# permamote.net
KiCad netlist of a schematic drawn in EAGLE
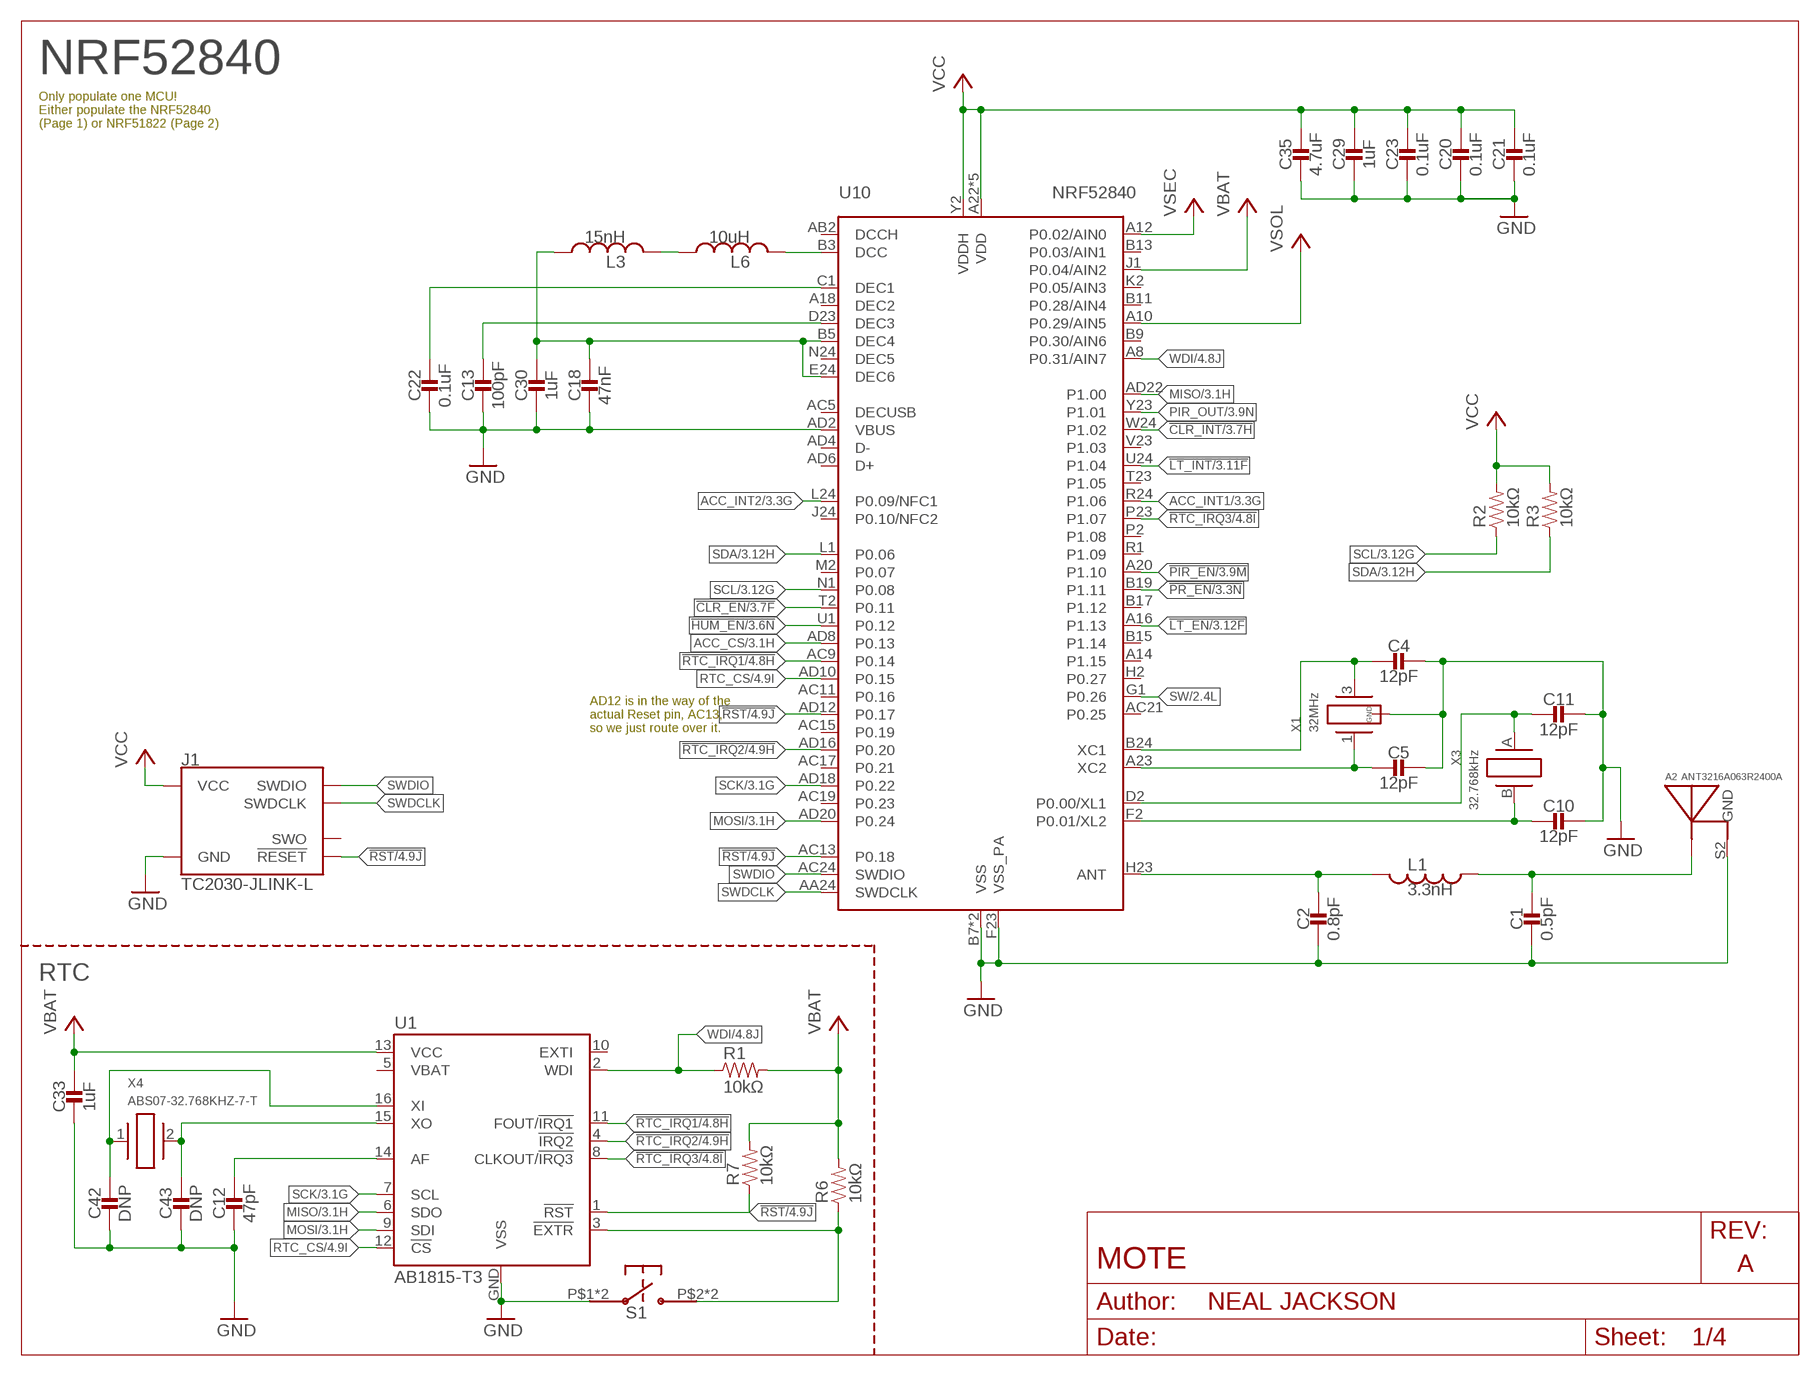
[diagram p0: schematic, sheet 1]
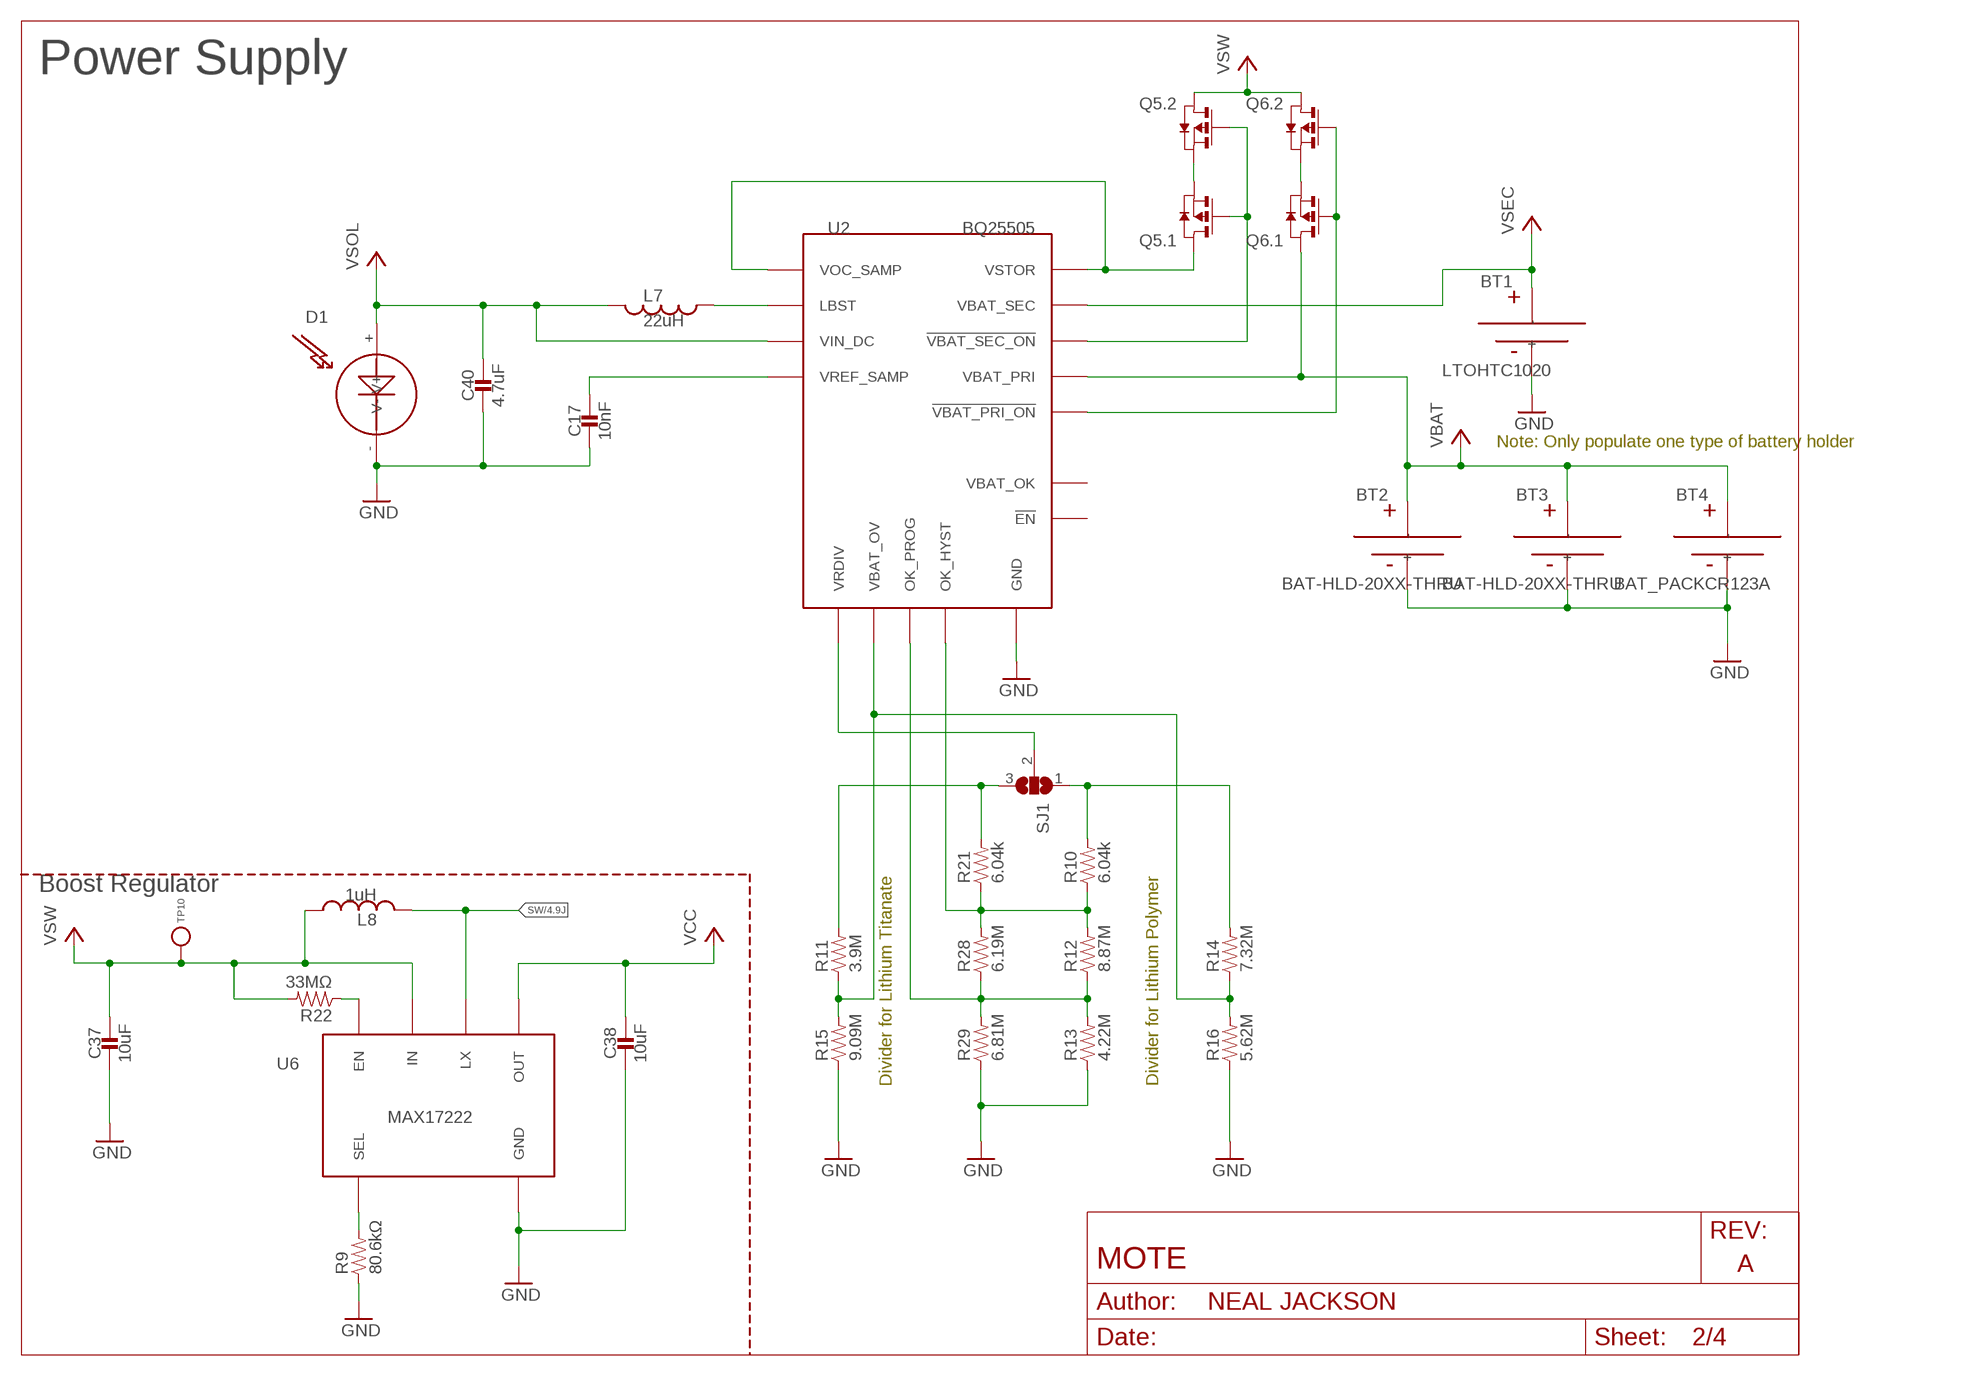
[diagram p1: schematic, sheet 2]
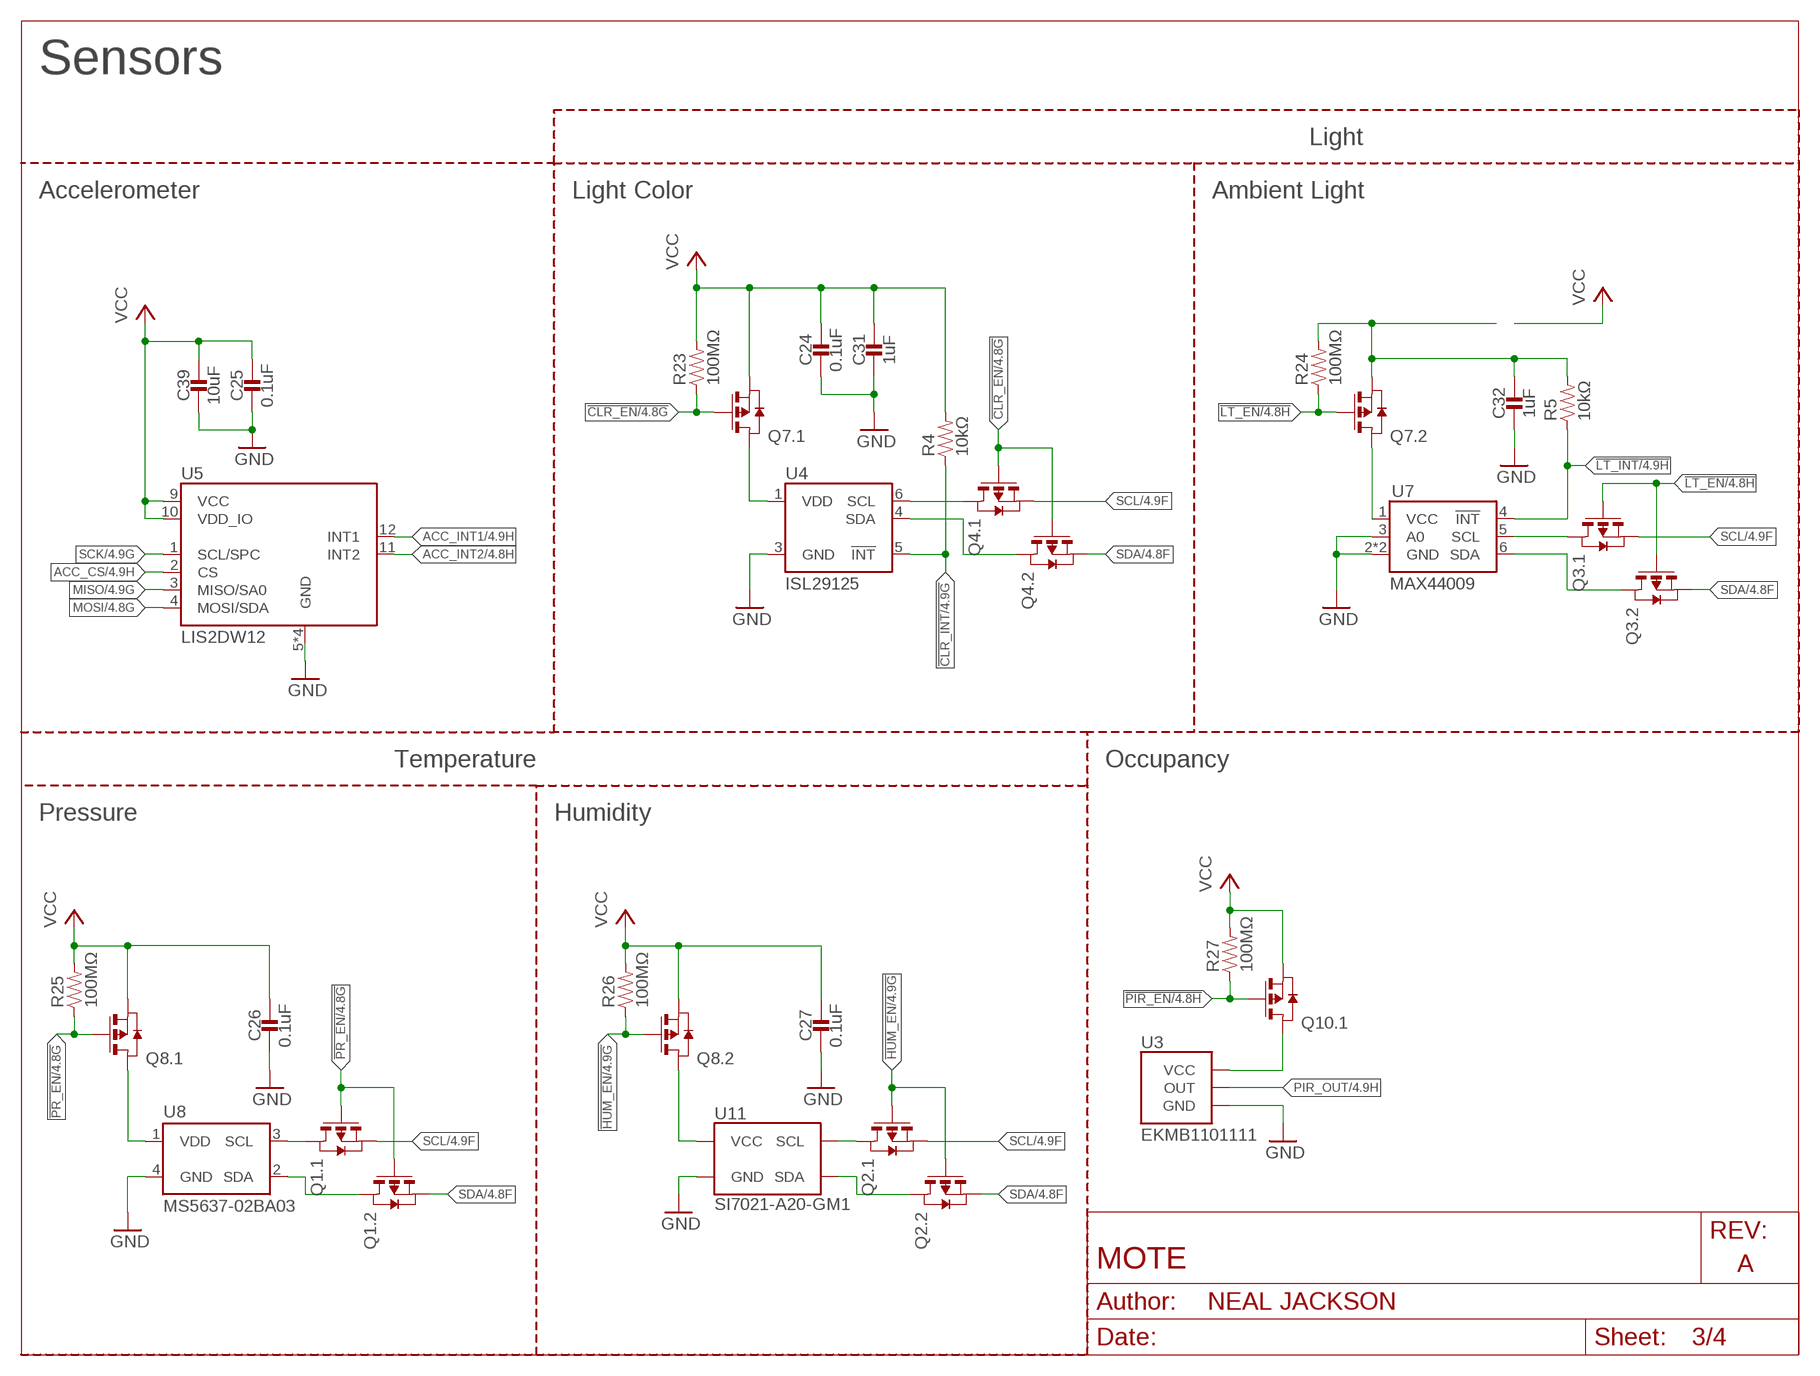
[diagram p2: schematic, sheet 3]
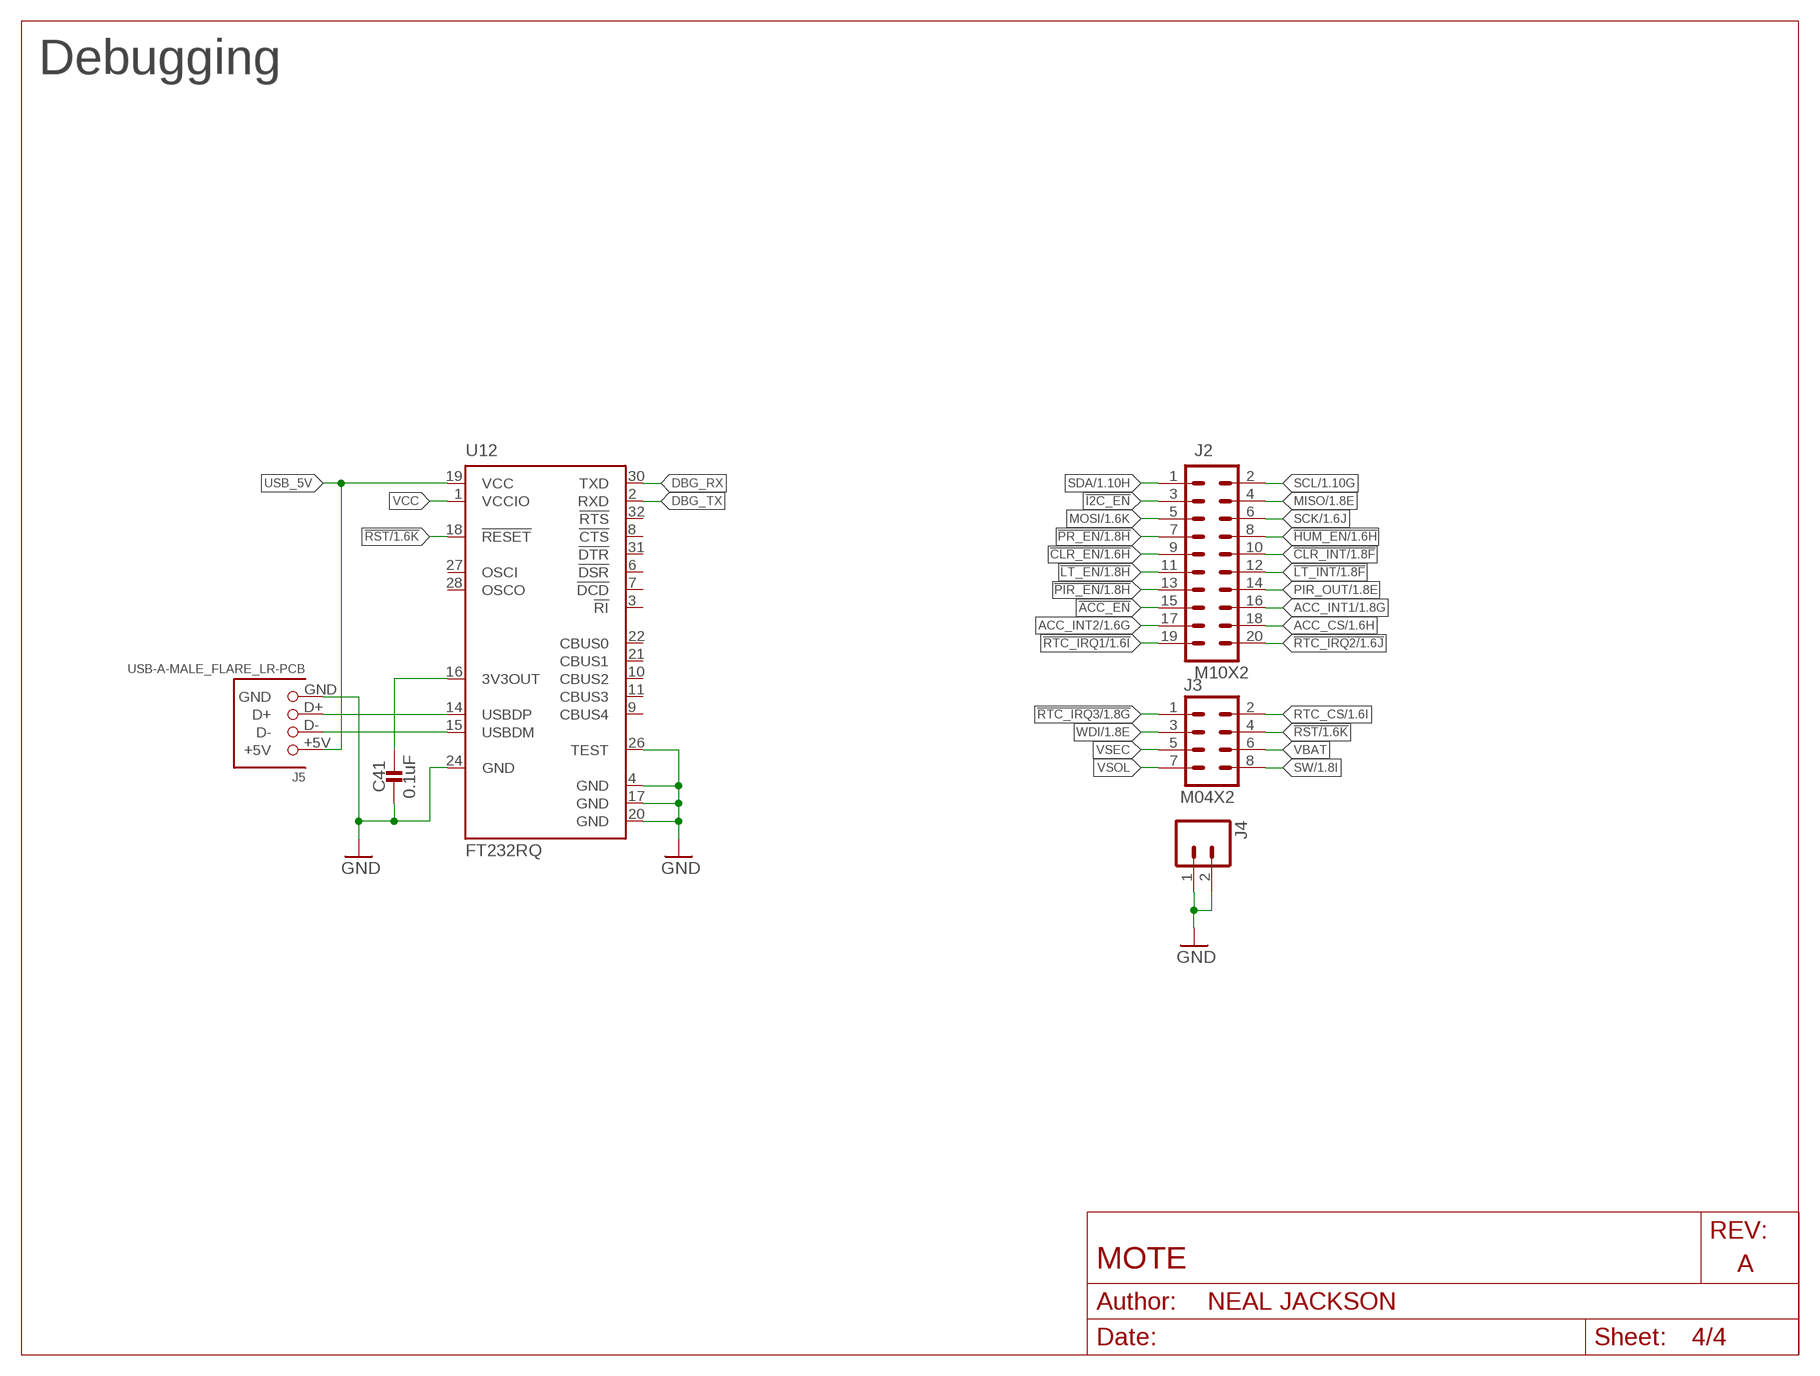
[diagram p3: schematic, sheet 4]

(export (version "E")
  (design (tool "Eeschema 10.0.6"))
  (components
    (comp (ref "BT1")
      (value "LTOHTC1020")
      (footprint "eagle-import:1020")
      (libsource (lib "eagle-import") (part "LTOHTC1020"))
    )
    (comp (ref "BT2")
      (value "BAT-HLD-20XX-THRU")
      (footprint "eagle-import:BAT-HLD-20XX-THRU")
      (fields (field (name "MANUFACTURER") "Linx Technologies") (field (name "MPN") "BAT-HLD-001-THM"))
      (libsource (lib "eagle-import") (part "BAT-HLD-20XX-THRU"))
    )
    (comp (ref "BT3")
      (value "BAT-HLD-20XX-THRU")
      (footprint "eagle-import:BAT-HLD-20XX-THRU")
      (fields (field (name "MANUFACTURER") "Linx Technologies") (field (name "MPN") "BAT-HLD-001-THM"))
      (libsource (lib "eagle-import") (part "BAT-HLD-20XX-THRU"))
    )
    (comp (ref "BT4")
      (value "BAT_PACKCR123A")
      (footprint "eagle-import:BH123A")
      (fields (field (name "MANUFACTURER") "MPD") (field (name "MPN") "BH123A"))
      (libsource (lib "eagle-import") (part "BAT_PACKCR123A"))
    )
    (comp (ref "C17")
      (value "10nF")
      (footprint "eagle-import:0603_CAP")
      (libsource (lib "eagle-import") (part "CAPACITOR0603_CAP"))
    )
    (comp (ref "C37")
      (value "10uF")
      (footprint "eagle-import:0603_CAP")
      (libsource (lib "eagle-import") (part "CAPACITOR0603_CAP"))
    )
    (comp (ref "C38")
      (value "10uF")
      (footprint "eagle-import:0603_CAP")
      (libsource (lib "eagle-import") (part "CAPACITOR0603_CAP"))
    )
    (comp (ref "C40")
      (value "4.7uF")
      (footprint "eagle-import:0603_CAP")
      (libsource (lib "eagle-import") (part "CAPACITOR0603_CAP"))
    )
    (comp (ref "D1")
      (value "SOLARCELL")
      (footprint "eagle-import:SOLAR_HOLES")
      (libsource (lib "eagle-import") (part "SOLARCELL"))
    )
    (comp (ref "L7")
      (value "22uH")
      (footprint "eagle-import:74437324220")
      (fields (field (name "DIGIKEY") "732-3340-1-ND"))
      (libsource (lib "eagle-import") (part "INDUCTOR74437324220"))
    )
    (comp (ref "L8")
      (value "1uH")
      (footprint "eagle-import:IHL-1212BZ-11")
      (fields
        (field (name "MANUFACTURER") "Vishay Dale")
        (field (name "MPN") "IHLP1212BZER2R2M11")
        (field (name "DIGIKEY") "541-1319-1-ND")
        (field (name "MPN_1") "IHLP1212BZER1R0M11")
      )
      (libsource (lib "eagle-import") (part "INDUCTORIHL"))
    )
    (comp (ref "Q5")
      (value "PMDXB950UPEL")
      (footprint "eagle-import:XDFN-6")
      (fields (field (name "MANUFACTURER") "NEXPERIA") (field (name "MPN") "PMDXB950UPELZ"))
      (libsource (lib "eagle-import") (part "PMDXB950UPEL"))
    )
    (comp (ref "Q6")
      (value "PMDXB950UPEL")
      (footprint "eagle-import:XDFN-6")
      (fields (field (name "MANUFACTURER") "NEXPERIA") (field (name "MPN") "PMDXB950UPELZ"))
      (libsource (lib "eagle-import") (part "PMDXB950UPEL"))
    )
    (comp (ref "R9")
      (value "80.6kΩ")
      (footprint "eagle-import:0603-RES")
      (libsource (lib "eagle-import") (part "RESISTOR0603_RES"))
    )
    (comp (ref "R10")
      (value "6.04k")
      (footprint "eagle-import:0402_RES")
      (libsource (lib "eagle-import") (part "RESISTOR0402_RES"))
    )
    (comp (ref "R11")
      (value "3.9M")
      (footprint "eagle-import:0402_RES")
      (libsource (lib "eagle-import") (part "RESISTOR0402_RES"))
    )
    (comp (ref "R12")
      (value "8.87M")
      (footprint "eagle-import:0402_RES")
      (libsource (lib "eagle-import") (part "RESISTOR0402_RES"))
    )
    (comp (ref "R13")
      (value "4.22M")
      (footprint "eagle-import:0402_RES")
      (libsource (lib "eagle-import") (part "RESISTOR0402_RES"))
    )
    (comp (ref "R14")
      (value "7.32M")
      (footprint "eagle-import:0402_RES")
      (libsource (lib "eagle-import") (part "RESISTOR0402_RES"))
    )
    (comp (ref "R15")
      (value "9.09M")
      (footprint "eagle-import:0402_RES")
      (libsource (lib "eagle-import") (part "RESISTOR0402_RES"))
    )
    (comp (ref "R16")
      (value "5.62M")
      (footprint "eagle-import:0402_RES")
      (libsource (lib "eagle-import") (part "RESISTOR0402_RES"))
    )
    (comp (ref "R21")
      (value "6.04k")
      (footprint "eagle-import:0402_RES")
      (libsource (lib "eagle-import") (part "RESISTOR0402_RES"))
    )
    (comp (ref "R22")
      (value "33MΩ")
      (footprint "eagle-import:0603-RES")
      (libsource (lib "eagle-import") (part "RESISTOR0603_RES"))
    )
    (comp (ref "R28")
      (value "6.19M")
      (footprint "eagle-import:0402_RES")
      (libsource (lib "eagle-import") (part "RESISTOR0402_RES"))
    )
    (comp (ref "R29")
      (value "6.81M")
      (footprint "eagle-import:0402_RES")
      (libsource (lib "eagle-import") (part "RESISTOR0402_RES"))
    )
    (comp (ref "SJ1")
      (value "SJ2W")
      (footprint "eagle-import:SJ_2")
      (libsource (lib "eagle-import") (part "SJ2W"))
    )
    (comp (ref "TP10")
      (value "TEST_POINT_0.040IN")
      (footprint "eagle-import:TESTPOINT_0.040IN")
      (libsource (lib "eagle-import") (part "TEST_POINT_0.040IN"))
    )
    (comp (ref "U2")
      (value "BQ25505")
      (footprint "eagle-import:S-PVQFN-N20-RGR")
      (fields (field (name "MANUFACTURER") "TI") (field (name "MPN") "BQ25505RGRR"))
      (libsource (lib "eagle-import") (part "BQ25505"))
    )
    (comp (ref "U6")
      (value "MAX17222")
      (footprint "eagle-import:UDFN-6-MAXIM")
      (fields (field (name "MANUFACTURER") "MAXIM INTEGRATED") (field (name "MPN") "MAX17222ELT+T"))
      (libsource (lib "eagle-import") (part "MAX17222"))
    )
    (comp (ref "C24")
      (value "0.1uF")
      (footprint "eagle-import:0402_CAP")
      (libsource (lib "eagle-import") (part "CAPACITOR0402_CAP"))
    )
    (comp (ref "C25")
      (value "0.1uF")
      (footprint "eagle-import:0402_CAP")
      (libsource (lib "eagle-import") (part "CAPACITOR0402_CAP"))
    )
    (comp (ref "C26")
      (value "0.1uF")
      (footprint "eagle-import:0402_CAP")
      (libsource (lib "eagle-import") (part "CAPACITOR0402_CAP"))
    )
    (comp (ref "C27")
      (value "0.1uF")
      (footprint "eagle-import:0402_CAP")
      (libsource (lib "eagle-import") (part "CAPACITOR0402_CAP"))
    )
    (comp (ref "C31")
      (value "1uF")
      (footprint "eagle-import:0402_CAP")
      (libsource (lib "eagle-import") (part "CAPACITOR0402_CAP"))
    )
    (comp (ref "C32")
      (value "1uF")
      (footprint "eagle-import:0402_CAP")
      (libsource (lib "eagle-import") (part "CAPACITOR0402_CAP"))
    )
    (comp (ref "C39")
      (value "10uF")
      (footprint "eagle-import:0603_CAP")
      (libsource (lib "eagle-import") (part "CAPACITOR0603_CAP"))
    )
    (comp (ref "Q1")
      (value "PMDXB950UPEL")
      (footprint "eagle-import:XDFN-6")
      (fields (field (name "MANUFACTURER") "NEXPERIA") (field (name "MPN") "PMDXB950UPELZ"))
      (libsource (lib "eagle-import") (part "PMDXB950UPEL"))
    )
    (comp (ref "Q2")
      (value "PMDXB950UPEL")
      (footprint "eagle-import:XDFN-6")
      (fields (field (name "MANUFACTURER") "NEXPERIA") (field (name "MPN") "PMDXB950UPELZ"))
      (libsource (lib "eagle-import") (part "PMDXB950UPEL"))
    )
    (comp (ref "Q3")
      (value "PMDXB950UPEL")
      (footprint "eagle-import:XDFN-6")
      (fields (field (name "MANUFACTURER") "NEXPERIA") (field (name "MPN") "PMDXB950UPELZ"))
      (libsource (lib "eagle-import") (part "PMDXB950UPEL"))
    )
    (comp (ref "Q4")
      (value "PMDXB950UPEL")
      (footprint "eagle-import:XDFN-6")
      (fields (field (name "MANUFACTURER") "NEXPERIA") (field (name "MPN") "PMDXB950UPELZ"))
      (libsource (lib "eagle-import") (part "PMDXB950UPEL"))
    )
    (comp (ref "Q7")
      (value "PMDXB950UPEL")
      (footprint "eagle-import:XDFN-6")
      (fields (field (name "MANUFACTURER") "NEXPERIA") (field (name "MPN") "PMDXB950UPELZ"))
      (libsource (lib "eagle-import") (part "PMDXB950UPEL"))
    )
    (comp (ref "Q8")
      (value "PMDXB950UPEL")
      (footprint "eagle-import:XDFN-6")
      (fields (field (name "MANUFACTURER") "NEXPERIA") (field (name "MPN") "PMDXB950UPELZ"))
      (libsource (lib "eagle-import") (part "PMDXB950UPEL"))
    )
    (comp (ref "Q10")
      (value "PMDXB950UPEL")
      (footprint "eagle-import:XDFN-6")
      (fields (field (name "MANUFACTURER") "NEXPERIA") (field (name "MPN") "PMDXB950UPELZ"))
      (libsource (lib "eagle-import") (part "PMDXB950UPEL"))
    )
    (comp (ref "R4")
      (value "10kΩ")
      (footprint "eagle-import:0402_RES")
      (libsource (lib "eagle-import") (part "RESISTOR0402_RES"))
    )
    (comp (ref "R5")
      (value "10kΩ")
      (footprint "eagle-import:0402_RES")
      (libsource (lib "eagle-import") (part "RESISTOR0402_RES"))
    )
    (comp (ref "R23")
      (value "100MΩ")
      (footprint "eagle-import:0402_RES")
      (libsource (lib "eagle-import") (part "RESISTOR0402_RES"))
    )
    (comp (ref "R24")
      (value "100MΩ")
      (footprint "eagle-import:0402_RES")
      (libsource (lib "eagle-import") (part "RESISTOR0402_RES"))
    )
    (comp (ref "R25")
      (value "100MΩ")
      (footprint "eagle-import:0402_RES")
      (libsource (lib "eagle-import") (part "RESISTOR0402_RES"))
    )
    (comp (ref "R26")
      (value "100MΩ")
      (footprint "eagle-import:0402_RES")
      (libsource (lib "eagle-import") (part "RESISTOR0402_RES"))
    )
    (comp (ref "R27")
      (value "100MΩ")
      (footprint "eagle-import:0402_RES")
      (libsource (lib "eagle-import") (part "RESISTOR0402_RES"))
    )
    (comp (ref "U3")
      (value "EKMB1101111")
      (footprint "eagle-import:AMN2")
      (fields (field (name "MANUFACTURER") "PANASONIC"))
      (libsource (lib "eagle-import") (part "EKMB1101111"))
    )
    (comp (ref "U4")
      (value "ISL29125")
      (footprint "eagle-import:ODFN-6-1.5MMX1.6MM")
      (fields (field (name "MANUFACTURER") "INTERSIL") (field (name "MPN") "ISL29125IROZ-T7A"))
      (libsource (lib "eagle-import") (part "ISL29125"))
    )
    (comp (ref "U5")
      (value "LIS2DW12")
      (footprint "eagle-import:LGA-12")
      (fields (field (name "MANUFACTURER") "STMicroelectronics") (field (name "MPN") "LIS2DW12TR"))
      (libsource (lib "eagle-import") (part "LIS2DW12"))
    )
    (comp (ref "U7")
      (value "MAX44009")
      (footprint "eagle-import:UDFN-6-EXPOSED")
      (fields (field (name "MANUFACTURER") "MAXIM") (field (name "MPN") "MAX44009EDT+T"))
      (libsource (lib "eagle-import") (part "MAX44009"))
    )
    (comp (ref "U8")
      (value "MS5637-02BA03")
      (footprint "eagle-import:4-SMD")
      (fields (field (name "MANUFACTURER") "TE CONNECTIVITY") (field (name "MPN") "MS563702BA03-50"))
      (libsource (lib "eagle-import") (part "MS5637-02BA03"))
    )
    (comp (ref "U11")
      (value "SI7021-A20-GM1")
      (footprint "eagle-import:DFN-6_3MM")
      (libsource (lib "eagle-import") (part "SI7021-A20-GM1"))
    )
    (comp (ref "A2")
      (value "ANT3216A063R2400A")
      (footprint "eagle-import:ANT3216A063R2400A")
      (fields (field (name "MANUFACTURER") "YAGEO"))
      (libsource (lib "eagle-import") (part "ANT3216A063R2400A"))
    )
    (comp (ref "C1")
      (value "0.5pF")
      (footprint "eagle-import:0402_CAP")
      (libsource (lib "eagle-import") (part "CAPACITOR0402_CAP"))
    )
    (comp (ref "C2")
      (value "0.8pF")
      (footprint "eagle-import:0402_CAP")
      (libsource (lib "eagle-import") (part "CAPACITOR0402_CAP"))
    )
    (comp (ref "C4")
      (value "12pF")
      (footprint "eagle-import:0402_CAP")
      (libsource (lib "eagle-import") (part "CAPACITOR0402_CAP"))
    )
    (comp (ref "C5")
      (value "12pF")
      (footprint "eagle-import:0402_CAP")
      (libsource (lib "eagle-import") (part "CAPACITOR0402_CAP"))
    )
    (comp (ref "C10")
      (value "12pF")
      (footprint "eagle-import:0402_CAP")
      (libsource (lib "eagle-import") (part "CAPACITOR0402_CAP"))
    )
    (comp (ref "C11")
      (value "12pF")
      (footprint "eagle-import:0402_CAP")
      (libsource (lib "eagle-import") (part "CAPACITOR0402_CAP"))
    )
    (comp (ref "C12")
      (value "47pF")
      (footprint "eagle-import:0402_CAP")
      (libsource (lib "eagle-import") (part "CAPACITOR0402_CAP"))
    )
    (comp (ref "C13")
      (value "100pF")
      (footprint "eagle-import:0402_CAP")
      (libsource (lib "eagle-import") (part "CAPACITOR0402_CAP"))
    )
    (comp (ref "C18")
      (value "47nF")
      (footprint "eagle-import:0402_CAP")
      (libsource (lib "eagle-import") (part "CAPACITOR0402_CAP"))
    )
    (comp (ref "C20")
      (value "0.1uF")
      (footprint "eagle-import:0402_CAP")
      (libsource (lib "eagle-import") (part "CAPACITOR0402_CAP"))
    )
    (comp (ref "C21")
      (value "0.1uF")
      (footprint "eagle-import:0402_CAP")
      (libsource (lib "eagle-import") (part "CAPACITOR0402_CAP"))
    )
    (comp (ref "C22")
      (value "0.1uF")
      (footprint "eagle-import:0402_CAP")
      (libsource (lib "eagle-import") (part "CAPACITOR0402_CAP"))
    )
    (comp (ref "C23")
      (value "0.1uF")
      (footprint "eagle-import:0402_CAP")
      (libsource (lib "eagle-import") (part "CAPACITOR0402_CAP"))
    )
    (comp (ref "C29")
      (value "1uF")
      (footprint "eagle-import:0402_CAP")
      (libsource (lib "eagle-import") (part "CAPACITOR0402_CAP"))
    )
    (comp (ref "C30")
      (value "1uF")
      (footprint "eagle-import:0402_CAP")
      (libsource (lib "eagle-import") (part "CAPACITOR0402_CAP"))
    )
    (comp (ref "C33")
      (value "1uF")
      (footprint "eagle-import:0402_CAP")
      (libsource (lib "eagle-import") (part "CAPACITOR0402_CAP"))
    )
    (comp (ref "C35")
      (value "4.7uF")
      (footprint "eagle-import:0402_CAP")
      (libsource (lib "eagle-import") (part "CAPACITOR0402_CAP"))
    )
    (comp (ref "C42")
      (value "DNP")
      (footprint "eagle-import:0402_CAP")
      (libsource (lib "eagle-import") (part "CAPACITOR0402_CAP"))
    )
    (comp (ref "C43")
      (value "DNP")
      (footprint "eagle-import:0402_CAP")
      (libsource (lib "eagle-import") (part "CAPACITOR0402_CAP"))
    )
    (comp (ref "J1")
      (value "TC2030-JLINK-L")
      (footprint "eagle-import:TC2030-IDC")
      (libsource (lib "eagle-import") (part "TC2030-JLINK-L"))
    )
    (comp (ref "L1")
      (value "3.3nH")
      (footprint "eagle-import:0402_CAP")
      (libsource (lib "eagle-import") (part "INDUCTOR0402"))
    )
    (comp (ref "L3")
      (value "15nH")
      (footprint "eagle-import:0402_CAP")
      (libsource (lib "eagle-import") (part "INDUCTOR0402"))
    )
    (comp (ref "L6")
      (value "10uH")
      (footprint "eagle-import:0603_CAP")
      (libsource (lib "eagle-import") (part "INDUCTOR0603"))
    )
    (comp (ref "R1")
      (value "10kΩ")
      (footprint "eagle-import:0402_RES")
      (libsource (lib "eagle-import") (part "RESISTOR0402_RES"))
    )
    (comp (ref "R2")
      (value "10kΩ")
      (footprint "eagle-import:0402_RES")
      (libsource (lib "eagle-import") (part "RESISTOR0402_RES"))
    )
    (comp (ref "R3")
      (value "10kΩ")
      (footprint "eagle-import:0402_RES")
      (libsource (lib "eagle-import") (part "RESISTOR0402_RES"))
    )
    (comp (ref "R6")
      (value "10kΩ")
      (footprint "eagle-import:0402_RES")
      (libsource (lib "eagle-import") (part "RESISTOR0402_RES"))
    )
    (comp (ref "R7")
      (value "10kΩ")
      (footprint "eagle-import:0402_RES")
      (libsource (lib "eagle-import") (part "RESISTOR0402_RES"))
    )
    (comp (ref "S1")
      (value "EVQP2")
      (footprint "eagle-import:EVQP2")
      (libsource (lib "eagle-import") (part "EVQP2"))
    )
    (comp (ref "U1")
      (value "AB1815-T3")
      (footprint "eagle-import:QFN-16-3MM")
      (fields (field (name "MANUFACTURER") "Abracon"))
      (libsource (lib "eagle-import") (part "AB1815-T3"))
    )
    (comp (ref "U10")
      (value "NRF52840")
      (footprint "eagle-import:AQFN73")
      (fields (field (name "MANUFACTURER") "NORIDIC SEMICONDUCTOR"))
      (libsource (lib "eagle-import") (part "NRF52840"))
    )
    (comp (ref "X1")
      (value "32MHz")
      (footprint "eagle-import:TXC-7V")
      (fields (field (name "MANUFACTURER") "TXC CORPORATION") (field (name "MPN") "7M-32.000MAHV-T"))
      (libsource (lib "eagle-import") (part "7V-32.000MAHV-T"))
    )
    (comp (ref "X3")
      (value "32.768kHz")
      (footprint "eagle-import:ABS05")
      (fields (field (name "MANUFACTURER") "Abracon") (field (name "MPN") "ABS05-32.768KHZ-9-T"))
      (libsource (lib "eagle-import") (part "ABS05-32.768KHZ-9-T"))
    )
    (comp (ref "X4")
      (value "ABS07-32.768KHZ-7-T")
      (footprint "eagle-import:2-SMD")
      (fields (field (name "MANUFACTURER") "ABRACON") (field (name "MPN") "ABS07-32.768KHZ-7-T "))
      (libsource (lib "eagle-import") (part "ABS07-32.768KHZ-7-T"))
    )
    (comp (ref "C41")
      (value "0.1uF")
      (footprint "eagle-import:0402_CAP")
      (libsource (lib "eagle-import") (part "CAPACITOR0402_CAP"))
    )
    (comp (ref "J2")
      (value "M10X2")
      (footprint "eagle-import:2X10")
      (libsource (lib "eagle-import") (part "M10X2"))
    )
    (comp (ref "J3")
      (value "M04X2")
      (footprint "eagle-import:2X4")
      (libsource (lib "eagle-import") (part "M04X2"))
    )
    (comp (ref "J4")
      (value "M02PTH")
      (footprint "eagle-import:1X02")
      (libsource (lib "eagle-import") (part "M02PTH"))
    )
    (comp (ref "J5")
      (value "USB-A-MALE_FLARE_LR-PCB")
      (footprint "eagle-import:USB-A-MALE_FLARE_LR")
      (libsource (lib "eagle-import") (part "USB-A-MALE_FLARE_LR-PCB"))
    )
    (comp (ref "U12")
      (value "FT232RQ")
      (footprint "eagle-import:QFN32")
      (libsource (lib "eagle-import") (part "FT232RQ"))
    )
  )
  (nets
    (net (code "1") (name "ACC_CS") (class "Default")
      (node (ref "J2") (pin "18") (pinfunction "18_18") (pintype "passive"))
      (node (ref "U10") (pin "AD8") (pinfunction "P0.13_AD8") (pintype "bidirectional"))
      (node (ref "U5") (pin "2") (pinfunction "CS_2") (pintype "bidirectional"))
    )
    (net (code "2") (name "ACC_INT1") (class "Default")
      (node (ref "J2") (pin "16") (pinfunction "16_16") (pintype "passive"))
      (node (ref "U10") (pin "R24") (pinfunction "P1.06_R24") (pintype "bidirectional"))
      (node (ref "U5") (pin "12") (pinfunction "INT1_12") (pintype "bidirectional"))
    )
    (net (code "3") (name "ACC_INT2") (class "Default")
      (node (ref "J2") (pin "17") (pinfunction "17_17") (pintype "passive"))
      (node (ref "U10") (pin "L24") (pinfunction "P0.09/NFC1_L24") (pintype "bidirectional"))
      (node (ref "U5") (pin "11") (pinfunction "INT2_11") (pintype "bidirectional"))
    )
    (net (code "4") (name "DBG_RX") (class "Default")
      (node (ref "U12") (pin "30") (pinfunction "TXD_30") (pintype "output"))
    )
    (net (code "5") (name "DBG_TX") (class "Default")
      (node (ref "U12") (pin "2") (pinfunction "RXD_2") (pintype "input"))
    )
    (net (code "6") (name "GND") (class "Default")
      (node (ref "A2") (pin "S2") (pinfunction "GND_S2") (pintype "bidirectional"))
      (node (ref "BT1") (pin "-") (pinfunction "-_-") (pintype "bidirectional"))
      (node (ref "BT2") (pin "GND") (pinfunction "-_GND") (pintype "bidirectional"))
      (node (ref "BT3") (pin "GND") (pinfunction "-_GND") (pintype "bidirectional"))
      (node (ref "BT4") (pin "-") (pinfunction "-_-") (pintype "bidirectional"))
      (node (ref "C1") (pin "2") (pinfunction "2_2") (pintype "bidirectional"))
      (node (ref "C10") (pin "1") (pinfunction "1_1") (pintype "bidirectional"))
      (node (ref "C11") (pin "1") (pinfunction "1_1") (pintype "bidirectional"))
      (node (ref "C12") (pin "2") (pinfunction "2_2") (pintype "bidirectional"))
      (node (ref "C13") (pin "2") (pinfunction "2_2") (pintype "bidirectional"))
      (node (ref "C17") (pin "2") (pinfunction "2_2") (pintype "bidirectional"))
      (node (ref "C18") (pin "2") (pinfunction "2_2") (pintype "bidirectional"))
      (node (ref "C2") (pin "2") (pinfunction "2_2") (pintype "bidirectional"))
      (node (ref "C20") (pin "2") (pinfunction "2_2") (pintype "bidirectional"))
      (node (ref "C21") (pin "2") (pinfunction "2_2") (pintype "bidirectional"))
      (node (ref "C22") (pin "2") (pinfunction "2_2") (pintype "bidirectional"))
      (node (ref "C23") (pin "2") (pinfunction "2_2") (pintype "bidirectional"))
      (node (ref "C24") (pin "2") (pinfunction "2_2") (pintype "bidirectional"))
      (node (ref "C25") (pin "2") (pinfunction "2_2") (pintype "bidirectional"))
      (node (ref "C26") (pin "2") (pinfunction "2_2") (pintype "bidirectional"))
      (node (ref "C27") (pin "2") (pinfunction "2_2") (pintype "bidirectional"))
      (node (ref "C29") (pin "2") (pinfunction "2_2") (pintype "bidirectional"))
      (node (ref "C30") (pin "2") (pinfunction "2_2") (pintype "bidirectional"))
      (node (ref "C31") (pin "2") (pinfunction "2_2") (pintype "bidirectional"))
      (node (ref "C32") (pin "2") (pinfunction "2_2") (pintype "bidirectional"))
      (node (ref "C33") (pin "2") (pinfunction "2_2") (pintype "bidirectional"))
      (node (ref "C35") (pin "2") (pinfunction "2_2") (pintype "bidirectional"))
      (node (ref "C37") (pin "2") (pinfunction "2_2") (pintype "bidirectional"))
      (node (ref "C38") (pin "2") (pinfunction "2_2") (pintype "bidirectional"))
      (node (ref "C39") (pin "2") (pinfunction "2_2") (pintype "bidirectional"))
      (node (ref "C4") (pin "1") (pinfunction "1_1") (pintype "bidirectional"))
      (node (ref "C40") (pin "2") (pinfunction "2_2") (pintype "bidirectional"))
      (node (ref "C41") (pin "2") (pinfunction "2_2") (pintype "bidirectional"))
      (node (ref "C42") (pin "2") (pinfunction "2_2") (pintype "bidirectional"))
      (node (ref "C43") (pin "2") (pinfunction "2_2") (pintype "bidirectional"))
      (node (ref "C5") (pin "1") (pinfunction "1_1") (pintype "bidirectional"))
      (node (ref "D1") (pin "-") (pinfunction "V-_-") (pintype "bidirectional"))
      (node (ref "J1") (pin "5") (pinfunction "GND_5") (pintype "bidirectional"))
      (node (ref "J4") (pin "1") (pinfunction "1_1") (pintype "passive"))
      (node (ref "J4") (pin "2") (pinfunction "2_2") (pintype "passive"))
      (node (ref "J5") (pin "GND") (pinfunction "GND_GND") (pintype "bidirectional"))
      (node (ref "R13") (pin "1") (pinfunction "1_1") (pintype "passive"))
      (node (ref "R15") (pin "1") (pinfunction "1_1") (pintype "passive"))
      (node (ref "R16") (pin "1") (pinfunction "1_1") (pintype "passive"))
      (node (ref "R29") (pin "1") (pinfunction "1_1") (pintype "passive"))
      (node (ref "R9") (pin "1") (pinfunction "1_1") (pintype "passive"))
      (node (ref "S1") (pin "P$1") (pinfunction "P$1_P$1") (pintype "passive"))
      (node (ref "S1") (pin "P$3") (pinfunction "P$1_P$3") (pintype "passive"))
      (node (ref "U1") (pin "GND") (pinfunction "VSS_GND") (pintype "bidirectional"))
      (node (ref "U10") (pin "AD2") (pinfunction "VBUS_AD2") (pintype "bidirectional"))
      (node (ref "U10") (pin "B7") (pinfunction "VSS_B7") (pintype "bidirectional"))
      (node (ref "U10") (pin "F23") (pinfunction "VSS_PA_F23") (pintype "bidirectional"))
      (node (ref "U10") (pin "GND") (pinfunction "VSS_GND") (pintype "bidirectional"))
      (node (ref "U11") (pin "2") (pinfunction "GND_2") (pintype "bidirectional"))
      (node (ref "U12") (pin "17") (pinfunction "GND_17") (pintype "power_in"))
      (node (ref "U12") (pin "20") (pinfunction "GND_20") (pintype "power_in"))
      (node (ref "U12") (pin "24") (pinfunction "GND_24") (pintype "power_in"))
      (node (ref "U12") (pin "26") (pinfunction "TEST_26") (pintype "input"))
      (node (ref "U12") (pin "4") (pinfunction "GND_4") (pintype "power_in"))
      (node (ref "U2") (pin "1") (pinfunction "GND_1") (pintype "bidirectional"))
      (node (ref "U2") (pin "15") (pinfunction "GND_15") (pintype "bidirectional"))
      (node (ref "U2") (pin "16") (pinfunction "GND_16") (pintype "bidirectional"))
      (node (ref "U2") (pin "17") (pinfunction "GND_17") (pintype "bidirectional"))
      (node (ref "U2") (pin "6") (pinfunction "GND_6") (pintype "bidirectional"))
      (node (ref "U2") (pin "PAD") (pinfunction "GND_PAD") (pintype "bidirectional"))
      (node (ref "U3") (pin "GND") (pinfunction "GND_GND") (pintype "bidirectional"))
      (node (ref "U4") (pin "3") (pinfunction "GND_3") (pintype "bidirectional"))
      (node (ref "U5") (pin "5") (pinfunction "GND_5") (pintype "bidirectional"))
      (node (ref "U5") (pin "6") (pinfunction "GND_6") (pintype "bidirectional"))
      (node (ref "U5") (pin "7") (pinfunction "GND_7") (pintype "bidirectional"))
      (node (ref "U5") (pin "8") (pinfunction "GND_8") (pintype "bidirectional"))
      (node (ref "U6") (pin "3") (pinfunction "GND_3") (pintype "bidirectional"))
      (node (ref "U7") (pin "2") (pinfunction "GND_2") (pintype "bidirectional"))
      (node (ref "U7") (pin "3") (pinfunction "A0_3") (pintype "bidirectional"))
      (node (ref "U7") (pin "EP") (pinfunction "GND_EP") (pintype "bidirectional"))
      (node (ref "U8") (pin "4") (pinfunction "GND_4") (pintype "bidirectional"))
      (node (ref "X1") (pin "2") (pinfunction "GND_2") (pintype "bidirectional"))
      (node (ref "X1") (pin "4") (pinfunction "GND_4") (pintype "bidirectional"))
    )
    (net (code "7") (name "MISO") (class "Default")
      (node (ref "J2") (pin "4") (pinfunction "4_4") (pintype "passive"))
      (node (ref "U1") (pin "6") (pinfunction "SDO_6") (pintype "bidirectional"))
      (node (ref "U10") (pin "AD22") (pinfunction "P1.00_AD22") (pintype "bidirectional"))
      (node (ref "U5") (pin "3") (pinfunction "MISO/SA0_3") (pintype "bidirectional"))
    )
    (net (code "8") (name "MOSI") (class "Default")
      (node (ref "J2") (pin "5") (pinfunction "5_5") (pintype "passive"))
      (node (ref "U1") (pin "9") (pinfunction "SDI_9") (pintype "bidirectional"))
      (node (ref "U10") (pin "AD20") (pinfunction "P0.24_AD20") (pintype "bidirectional"))
      (node (ref "U5") (pin "4") (pinfunction "MOSI/SDA_4") (pintype "bidirectional"))
    )
    (net (code "9") (name "Net-(A2-ANTENNA)") (class "Default")
      (node (ref "A2") (pin "S1") (pinfunction "ANTENNA_S1") (pintype "bidirectional"))
      (node (ref "C1") (pin "1") (pinfunction "1_1") (pintype "bidirectional"))
      (node (ref "L1") (pin "1") (pinfunction "1_1") (pintype "bidirectional"))
    )
    (net (code "10") (name "Net-(L3-Pad2)") (class "Default")
      (node (ref "L3") (pin "2") (pinfunction "2_2") (pintype "bidirectional"))
      (node (ref "L6") (pin "1") (pinfunction "1_1") (pintype "bidirectional"))
    )
    (net (code "11") (name "Net-(L7-1)") (class "Default")
      (node (ref "L7") (pin "P$1") (pinfunction "1_P$1") (pintype "bidirectional"))
      (node (ref "U2") (pin "20") (pinfunction "LBST_20") (pintype "bidirectional"))
    )
    (net (code "12") (name "Net-(Q1A-D)") (class "Default")
      (node (ref "Q1") (pin "6") (pinfunction "D_6") (pintype "passive"))
      (node (ref "U8") (pin "3") (pinfunction "SCL_3") (pintype "bidirectional"))
    )
    (net (code "13") (name "Net-(Q1B-D)") (class "Default")
      (node (ref "Q1") (pin "3") (pinfunction "D_3") (pintype "passive"))
      (node (ref "U8") (pin "2") (pinfunction "SDA_2") (pintype "bidirectional"))
    )
    (net (code "14") (name "Net-(Q2A-D)") (class "Default")
      (node (ref "Q2") (pin "6") (pinfunction "D_6") (pintype "passive"))
      (node (ref "U11") (pin "6") (pinfunction "SCL_6") (pintype "bidirectional"))
    )
    (net (code "15") (name "Net-(Q2B-D)") (class "Default")
      (node (ref "Q2") (pin "3") (pinfunction "D_3") (pintype "passive"))
      (node (ref "U11") (pin "1") (pinfunction "SDA_1") (pintype "bidirectional"))
    )
    (net (code "16") (name "Net-(Q3A-D)") (class "Default")
      (node (ref "Q3") (pin "6") (pinfunction "D_6") (pintype "passive"))
      (node (ref "U7") (pin "5") (pinfunction "SCL_5") (pintype "bidirectional"))
    )
    (net (code "17") (name "Net-(Q3B-D)") (class "Default")
      (node (ref "Q3") (pin "3") (pinfunction "D_3") (pintype "passive"))
      (node (ref "U7") (pin "6") (pinfunction "SDA_6") (pintype "bidirectional"))
    )
    (net (code "18") (name "Net-(Q4A-D)") (class "Default")
      (node (ref "Q4") (pin "6") (pinfunction "D_6") (pintype "passive"))
      (node (ref "U4") (pin "6") (pinfunction "SCL_6") (pintype "bidirectional"))
    )
    (net (code "19") (name "Net-(Q4B-D)") (class "Default")
      (node (ref "Q4") (pin "3") (pinfunction "D_3") (pintype "passive"))
      (node (ref "U4") (pin "4") (pinfunction "SDA_4") (pintype "bidirectional"))
    )
    (net (code "20") (name "Net-(Q5A-D)") (class "Default")
      (node (ref "Q5") (pin "6") (pinfunction "D_6") (pintype "passive"))
      (node (ref "U2") (pin "19") (pinfunction "VSTOR_19") (pintype "bidirectional"))
      (node (ref "U2") (pin "3") (pinfunction "VOC_SAMP_3") (pintype "bidirectional"))
    )
    (net (code "21") (name "Net-(Q5A-G)") (class "Default")
      (node (ref "Q5") (pin "2") (pinfunction "G_2") (pintype "passive"))
      (node (ref "Q5") (pin "5") (pinfunction "G_5") (pintype "passive"))
      (node (ref "U2") (pin "9") (pinfunction "~{VBAT_SEC_ON}_9") (pintype "bidirectional"))
    )
    (net (code "22") (name "Net-(Q5A-S)") (class "Default")
      (node (ref "Q5") (pin "1") (pinfunction "S_1") (pintype "passive"))
      (node (ref "Q5") (pin "4") (pinfunction "S_4") (pintype "passive"))
    )
    (net (code "23") (name "Net-(Q6A-G)") (class "Default")
      (node (ref "Q6") (pin "2") (pinfunction "G_2") (pintype "passive"))
      (node (ref "Q6") (pin "5") (pinfunction "G_5") (pintype "passive"))
      (node (ref "U2") (pin "10") (pinfunction "~{VBAT_PRI_ON}_10") (pintype "bidirectional"))
    )
    (net (code "24") (name "Net-(Q6A-S)") (class "Default")
      (node (ref "Q6") (pin "1") (pinfunction "S_1") (pintype "passive"))
      (node (ref "Q6") (pin "4") (pinfunction "S_4") (pintype "passive"))
    )
    (net (code "25") (name "Net-(Q7A-D)") (class "Default")
      (node (ref "Q7") (pin "6") (pinfunction "D_6") (pintype "passive"))
      (node (ref "U4") (pin "1") (pinfunction "VDD_1") (pintype "bidirectional"))
    )
    (net (code "26") (name "Net-(Q7B-D)") (class "Default")
      (node (ref "Q7") (pin "3") (pinfunction "D_3") (pintype "passive"))
      (node (ref "U7") (pin "1") (pinfunction "VCC_1") (pintype "bidirectional"))
    )
    (net (code "27") (name "Net-(Q7B-S)") (class "Default")
      (node (ref "C32") (pin "1") (pinfunction "1_1") (pintype "bidirectional"))
      (node (ref "Q7") (pin "4") (pinfunction "S_4") (pintype "passive"))
      (node (ref "R24") (pin "2") (pinfunction "2_2") (pintype "passive"))
      (node (ref "R5") (pin "2") (pinfunction "2_2") (pintype "passive"))
    )
    (net (code "28") (name "Net-(Q8A-D)") (class "Default")
      (node (ref "Q8") (pin "6") (pinfunction "D_6") (pintype "passive"))
      (node (ref "U8") (pin "1") (pinfunction "VDD_1") (pintype "bidirectional"))
    )
    (net (code "29") (name "Net-(Q8B-D)") (class "Default")
      (node (ref "Q8") (pin "3") (pinfunction "D_3") (pintype "passive"))
      (node (ref "U11") (pin "5") (pinfunction "VCC_5") (pintype "bidirectional"))
    )
    (net (code "30") (name "Net-(Q10A-D)") (class "Default")
      (node (ref "Q10") (pin "6") (pinfunction "D_6") (pintype "passive"))
      (node (ref "U3") (pin "VCC") (pinfunction "VCC_VCC") (pintype "bidirectional"))
    )
    (net (code "31") (name "Net-(R10-Pad2)") (class "Default")
      (node (ref "R10") (pin "2") (pinfunction "2_2") (pintype "passive"))
      (node (ref "R14") (pin "2") (pinfunction "2_2") (pintype "passive"))
      (node (ref "SJ1") (pin "1") (pinfunction "1_1") (pintype "passive"))
    )
    (net (code "32") (name "Net-(R11-Pad2)") (class "Default")
      (node (ref "R11") (pin "2") (pinfunction "2_2") (pintype "passive"))
      (node (ref "R21") (pin "2") (pinfunction "2_2") (pintype "passive"))
      (node (ref "SJ1") (pin "3") (pinfunction "3_3") (pintype "passive"))
    )
    (net (code "33") (name "Net-(U1-AF)") (class "Default")
      (node (ref "C12") (pin "1") (pinfunction "1_1") (pintype "bidirectional"))
      (node (ref "U1") (pin "14") (pinfunction "AF_14") (pintype "bidirectional"))
    )
    (net (code "34") (name "Net-(U1-XI)") (class "Default")
      (node (ref "C42") (pin "1") (pinfunction "1_1") (pintype "bidirectional"))
      (node (ref "U1") (pin "16") (pinfunction "XI_16") (pintype "bidirectional"))
      (node (ref "X4") (pin "1") (pinfunction "1_1") (pintype "bidirectional"))
    )
    (net (code "35") (name "Net-(U1-XO)") (class "Default")
      (node (ref "C43") (pin "1") (pinfunction "1_1") (pintype "bidirectional"))
      (node (ref "U1") (pin "15") (pinfunction "XO_15") (pintype "bidirectional"))
      (node (ref "X4") (pin "2") (pinfunction "2_2") (pintype "bidirectional"))
    )
    (net (code "36") (name "Net-(U1-~{EXTR})") (class "Default")
      (node (ref "R6") (pin "1") (pinfunction "1_1") (pintype "passive"))
      (node (ref "S1") (pin "P$2") (pinfunction "P$2_P$2") (pintype "passive"))
      (node (ref "S1") (pin "P$4") (pinfunction "P$2_P$4") (pintype "passive"))
      (node (ref "U1") (pin "3") (pinfunction "~{EXTR}_3") (pintype "bidirectional"))
    )
    (net (code "37") (name "Net-(U2-OK_HYST)") (class "Default")
      (node (ref "R10") (pin "1") (pinfunction "1_1") (pintype "passive"))
      (node (ref "R12") (pin "2") (pinfunction "2_2") (pintype "passive"))
      (node (ref "R21") (pin "1") (pinfunction "1_1") (pintype "passive"))
      (node (ref "R28") (pin "2") (pinfunction "2_2") (pintype "passive"))
      (node (ref "U2") (pin "11") (pinfunction "OK_HYST_11") (pintype "bidirectional"))
    )
    (net (code "38") (name "Net-(U2-OK_PROG)") (class "Default")
      (node (ref "R12") (pin "1") (pinfunction "1_1") (pintype "passive"))
      (node (ref "R13") (pin "2") (pinfunction "2_2") (pintype "passive"))
      (node (ref "R28") (pin "1") (pinfunction "1_1") (pintype "passive"))
      (node (ref "R29") (pin "2") (pinfunction "2_2") (pintype "passive"))
      (node (ref "U2") (pin "12") (pinfunction "OK_PROG_12") (pintype "bidirectional"))
    )
    (net (code "39") (name "Net-(U2-VBAT_OV)") (class "Default")
      (node (ref "R11") (pin "1") (pinfunction "1_1") (pintype "passive"))
      (node (ref "R14") (pin "1") (pinfunction "1_1") (pintype "passive"))
      (node (ref "R15") (pin "2") (pinfunction "2_2") (pintype "passive"))
      (node (ref "R16") (pin "2") (pinfunction "2_2") (pintype "passive"))
      (node (ref "U2") (pin "7") (pinfunction "VBAT_OV_7") (pintype "bidirectional"))
    )
    (net (code "40") (name "Net-(U2-VRDIV)") (class "Default")
      (node (ref "SJ1") (pin "2") (pinfunction "2_2") (pintype "passive"))
      (node (ref "U2") (pin "8") (pinfunction "VRDIV_8") (pintype "bidirectional"))
    )
    (net (code "41") (name "Net-(U2-VREF_SAMP)") (class "Default")
      (node (ref "C17") (pin "1") (pinfunction "1_1") (pintype "bidirectional"))
      (node (ref "U2") (pin "4") (pinfunction "VREF_SAMP_4") (pintype "bidirectional"))
    )
    (net (code "42") (name "Net-(U6-EN)") (class "Default")
      (node (ref "R22") (pin "1") (pinfunction "1_1") (pintype "passive"))
      (node (ref "U6") (pin "6") (pinfunction "EN_6") (pintype "bidirectional"))
    )
    (net (code "43") (name "Net-(U6-SEL)") (class "Default")
      (node (ref "R9") (pin "2") (pinfunction "2_2") (pintype "passive"))
      (node (ref "U6") (pin "4") (pinfunction "SEL_4") (pintype "bidirectional"))
    )
    (net (code "44") (name "Net-(U10-ANT)") (class "Default")
      (node (ref "C2") (pin "1") (pinfunction "1_1") (pintype "bidirectional"))
      (node (ref "L1") (pin "2") (pinfunction "2_2") (pintype "bidirectional"))
      (node (ref "U10") (pin "H23") (pinfunction "ANT_H23") (pintype "bidirectional"))
    )
    (net (code "45") (name "Net-(U10-DCC)") (class "Default")
      (node (ref "L6") (pin "2") (pinfunction "2_2") (pintype "bidirectional"))
      (node (ref "U10") (pin "B3") (pinfunction "DCC_B3") (pintype "bidirectional"))
    )
    (net (code "46") (name "Net-(U10-DEC1)") (class "Default")
      (node (ref "C22") (pin "1") (pinfunction "1_1") (pintype "bidirectional"))
      (node (ref "U10") (pin "C1") (pinfunction "DEC1_C1") (pintype "bidirectional"))
    )
    (net (code "47") (name "Net-(U10-DEC3)") (class "Default")
      (node (ref "C13") (pin "1") (pinfunction "1_1") (pintype "bidirectional"))
      (node (ref "U10") (pin "D23") (pinfunction "DEC3_D23") (pintype "bidirectional"))
    )
    (net (code "48") (name "Net-(U10-DEC4)") (class "Default")
      (node (ref "C18") (pin "1") (pinfunction "1_1") (pintype "bidirectional"))
      (node (ref "C30") (pin "1") (pinfunction "1_1") (pintype "bidirectional"))
      (node (ref "L3") (pin "1") (pinfunction "1_1") (pintype "bidirectional"))
      (node (ref "U10") (pin "B5") (pinfunction "DEC4_B5") (pintype "bidirectional"))
      (node (ref "U10") (pin "E24") (pinfunction "DEC6_E24") (pintype "bidirectional"))
    )
    (net (code "49") (name "Net-(U10-P0.00{slash}XL1)") (class "Default")
      (node (ref "C11") (pin "2") (pinfunction "2_2") (pintype "bidirectional"))
      (node (ref "U10") (pin "D2") (pinfunction "P0.00/XL1_D2") (pintype "bidirectional"))
      (node (ref "X3") (pin "A") (pinfunction "1_A") (pintype "bidirectional"))
    )
    (net (code "50") (name "Net-(U10-P0.01{slash}XL2)") (class "Default")
      (node (ref "C10") (pin "2") (pinfunction "2_2") (pintype "bidirectional"))
      (node (ref "U10") (pin "F2") (pinfunction "P0.01/XL2_F2") (pintype "bidirectional"))
      (node (ref "X3") (pin "B") (pinfunction "2_B") (pintype "bidirectional"))
    )
    (net (code "51") (name "Net-(U10-XC1)") (class "Default")
      (node (ref "C4") (pin "2") (pinfunction "2_2") (pintype "bidirectional"))
      (node (ref "U10") (pin "B24") (pinfunction "XC1_B24") (pintype "bidirectional"))
      (node (ref "X1") (pin "3") (pinfunction "2_3") (pintype "bidirectional"))
    )
    (net (code "52") (name "Net-(U10-XC2)") (class "Default")
      (node (ref "C5") (pin "2") (pinfunction "2_2") (pintype "bidirectional"))
      (node (ref "U10") (pin "A23") (pinfunction "XC2_A23") (pintype "bidirectional"))
      (node (ref "X1") (pin "1") (pinfunction "1_1") (pintype "bidirectional"))
    )
    (net (code "53") (name "Net-(U12-3V3OUT)") (class "Default")
      (node (ref "C41") (pin "1") (pinfunction "1_1") (pintype "bidirectional"))
      (node (ref "U12") (pin "16") (pinfunction "3V3OUT_16") (pintype "output"))
    )
    (net (code "54") (name "Net-(U12-USBDM)") (class "Default")
      (node (ref "J5") (pin "D-") (pinfunction "D-_D-") (pintype "bidirectional"))
      (node (ref "U12") (pin "15") (pinfunction "USBDM_15") (pintype "bidirectional"))
    )
    (net (code "55") (name "Net-(U12-USBDP)") (class "Default")
      (node (ref "J5") (pin "D+") (pinfunction "D+_D+") (pintype "bidirectional"))
      (node (ref "U12") (pin "14") (pinfunction "USBDP_14") (pintype "bidirectional"))
    )
    (net (code "56") (name "PIR_OUT") (class "Default")
      (node (ref "J2") (pin "14") (pinfunction "14_14") (pintype "passive"))
      (node (ref "U10") (pin "Y23") (pinfunction "P1.01_Y23") (pintype "bidirectional"))
      (node (ref "U3") (pin "OUT") (pinfunction "OUT_OUT") (pintype "bidirectional"))
    )
    (net (code "57") (name "RTC_CS") (class "Default")
      (node (ref "J3") (pin "2") (pinfunction "2_2") (pintype "passive"))
      (node (ref "U1") (pin "12") (pinfunction "~{CS}_12") (pintype "bidirectional"))
      (node (ref "U10") (pin "AD10") (pinfunction "P0.15_AD10") (pintype "bidirectional"))
    )
    (net (code "58") (name "SCK") (class "Default")
      (node (ref "J2") (pin "6") (pinfunction "6_6") (pintype "passive"))
      (node (ref "U1") (pin "7") (pinfunction "SCL_7") (pintype "bidirectional"))
      (node (ref "U10") (pin "AD18") (pinfunction "P0.22_AD18") (pintype "bidirectional"))
      (node (ref "U5") (pin "1") (pinfunction "SCL/SPC_1") (pintype "bidirectional"))
    )
    (net (code "59") (name "SCL") (class "Default")
      (node (ref "J2") (pin "2") (pinfunction "2_2") (pintype "passive"))
      (node (ref "Q1") (pin "1") (pinfunction "S_1") (pintype "passive"))
      (node (ref "Q2") (pin "1") (pinfunction "S_1") (pintype "passive"))
      (node (ref "Q3") (pin "1") (pinfunction "S_1") (pintype "passive"))
      (node (ref "Q4") (pin "1") (pinfunction "S_1") (pintype "passive"))
      (node (ref "R2") (pin "1") (pinfunction "1_1") (pintype "passive"))
      (node (ref "U10") (pin "N1") (pinfunction "P0.08_N1") (pintype "bidirectional"))
    )
    (net (code "60") (name "SDA") (class "Default")
      (node (ref "J2") (pin "1") (pinfunction "1_1") (pintype "passive"))
      (node (ref "Q1") (pin "4") (pinfunction "S_4") (pintype "passive"))
      (node (ref "Q2") (pin "4") (pinfunction "S_4") (pintype "passive"))
      (node (ref "Q3") (pin "4") (pinfunction "S_4") (pintype "passive"))
      (node (ref "Q4") (pin "4") (pinfunction "S_4") (pintype "passive"))
      (node (ref "R3") (pin "1") (pinfunction "1_1") (pintype "passive"))
      (node (ref "U10") (pin "L1") (pinfunction "P0.06_L1") (pintype "bidirectional"))
    )
    (net (code "61") (name "SW") (class "Default")
      (node (ref "J3") (pin "8") (pinfunction "8_8") (pintype "passive"))
      (node (ref "L8") (pin "P$2") (pinfunction "2_P$2") (pintype "bidirectional"))
      (node (ref "U10") (pin "G1") (pinfunction "P0.26_G1") (pintype "bidirectional"))
      (node (ref "U6") (pin "2") (pinfunction "LX_2") (pintype "bidirectional"))
    )
    (net (code "62") (name "SWDCLK") (class "Default")
      (node (ref "J1") (pin "4") (pinfunction "SWDCLK_4") (pintype "bidirectional"))
      (node (ref "U10") (pin "AA24") (pinfunction "SWDCLK_AA24") (pintype "bidirectional"))
    )
    (net (code "63") (name "SWDIO") (class "Default")
      (node (ref "J1") (pin "2") (pinfunction "SWDIO_2") (pintype "bidirectional"))
      (node (ref "U10") (pin "AC24") (pinfunction "SWDIO_AC24") (pintype "bidirectional"))
    )
    (net (code "64") (name "USB_5V") (class "Default")
      (node (ref "J5") (pin "+5V") (pinfunction "+5V_+5V") (pintype "bidirectional"))
      (node (ref "U12") (pin "19") (pinfunction "VCC_19") (pintype "power_in"))
    )
    (net (code "65") (name "VBAT") (class "Default")
      (node (ref "BT2") (pin "+1") (pinfunction "+_+1") (pintype "bidirectional"))
      (node (ref "BT2") (pin "+2") (pinfunction "+_+2") (pintype "bidirectional"))
      (node (ref "BT2") (pin "+3") (pinfunction "+_+3") (pintype "bidirectional"))
      (node (ref "BT2") (pin "+4") (pinfunction "+_+4") (pintype "bidirectional"))
      (node (ref "BT3") (pin "+1") (pinfunction "+_+1") (pintype "bidirectional"))
      (node (ref "BT3") (pin "+2") (pinfunction "+_+2") (pintype "bidirectional"))
      (node (ref "BT3") (pin "+3") (pinfunction "+_+3") (pintype "bidirectional"))
      (node (ref "BT3") (pin "+4") (pinfunction "+_+4") (pintype "bidirectional"))
      (node (ref "BT4") (pin "+") (pinfunction "+_+") (pintype "bidirectional"))
      (node (ref "C33") (pin "1") (pinfunction "1_1") (pintype "bidirectional"))
      (node (ref "J3") (pin "6") (pinfunction "6_6") (pintype "passive"))
      (node (ref "Q6") (pin "6") (pinfunction "D_6") (pintype "passive"))
      (node (ref "R1") (pin "2") (pinfunction "2_2") (pintype "passive"))
      (node (ref "R6") (pin "2") (pinfunction "2_2") (pintype "passive"))
      (node (ref "R7") (pin "2") (pinfunction "2_2") (pintype "passive"))
      (node (ref "U1") (pin "13") (pinfunction "VCC_13") (pintype "bidirectional"))
      (node (ref "U10") (pin "J1") (pinfunction "P0.04/AIN2_J1") (pintype "bidirectional"))
      (node (ref "U2") (pin "14") (pinfunction "VBAT_PRI_14") (pintype "bidirectional"))
    )
    (net (code "66") (name "VCC") (class "Default")
      (node (ref "C20") (pin "1") (pinfunction "1_1") (pintype "bidirectional"))
      (node (ref "C21") (pin "1") (pinfunction "1_1") (pintype "bidirectional"))
      (node (ref "C23") (pin "1") (pinfunction "1_1") (pintype "bidirectional"))
      (node (ref "C24") (pin "1") (pinfunction "1_1") (pintype "bidirectional"))
      (node (ref "C25") (pin "1") (pinfunction "1_1") (pintype "bidirectional"))
      (node (ref "C26") (pin "1") (pinfunction "1_1") (pintype "bidirectional"))
      (node (ref "C27") (pin "1") (pinfunction "1_1") (pintype "bidirectional"))
      (node (ref "C29") (pin "1") (pinfunction "1_1") (pintype "bidirectional"))
      (node (ref "C31") (pin "1") (pinfunction "1_1") (pintype "bidirectional"))
      (node (ref "C35") (pin "1") (pinfunction "1_1") (pintype "bidirectional"))
      (node (ref "C38") (pin "1") (pinfunction "1_1") (pintype "bidirectional"))
      (node (ref "C39") (pin "1") (pinfunction "1_1") (pintype "bidirectional"))
      (node (ref "J1") (pin "1") (pinfunction "VCC_1") (pintype "bidirectional"))
      (node (ref "Q10") (pin "1") (pinfunction "S_1") (pintype "passive"))
      (node (ref "Q7") (pin "1") (pinfunction "S_1") (pintype "passive"))
      (node (ref "Q8") (pin "1") (pinfunction "S_1") (pintype "passive"))
      (node (ref "Q8") (pin "4") (pinfunction "S_4") (pintype "passive"))
      (node (ref "R2") (pin "2") (pinfunction "2_2") (pintype "passive"))
      (node (ref "R23") (pin "2") (pinfunction "2_2") (pintype "passive"))
      (node (ref "R25") (pin "2") (pinfunction "2_2") (pintype "passive"))
      (node (ref "R26") (pin "2") (pinfunction "2_2") (pintype "passive"))
      (node (ref "R27") (pin "2") (pinfunction "2_2") (pintype "passive"))
      (node (ref "R3") (pin "2") (pinfunction "2_2") (pintype "passive"))
      (node (ref "R4") (pin "2") (pinfunction "2_2") (pintype "passive"))
      (node (ref "U10") (pin "A22") (pinfunction "VDD_A22") (pintype "bidirectional"))
      (node (ref "U10") (pin "AD14") (pinfunction "VDD_AD14") (pintype "bidirectional"))
      (node (ref "U10") (pin "AD23") (pinfunction "VDD_AD23") (pintype "bidirectional"))
      (node (ref "U10") (pin "B1") (pinfunction "VDD_B1") (pintype "bidirectional"))
      (node (ref "U10") (pin "W1") (pinfunction "VDD_W1") (pintype "bidirectional"))
      (node (ref "U10") (pin "Y2") (pinfunction "VDDH_Y2") (pintype "bidirectional"))
      (node (ref "U12") (pin "1") (pinfunction "VCCIO_1") (pintype "power_in"))
      (node (ref "U5") (pin "10") (pinfunction "VDD_IO_10") (pintype "bidirectional"))
      (node (ref "U5") (pin "9") (pinfunction "VCC_9") (pintype "bidirectional"))
      (node (ref "U6") (pin "1") (pinfunction "OUT_1") (pintype "bidirectional"))
    )
    (net (code "67") (name "VSEC") (class "Default")
      (node (ref "BT1") (pin "+") (pinfunction "+_+") (pintype "bidirectional"))
      (node (ref "J3") (pin "5") (pinfunction "5_5") (pintype "passive"))
      (node (ref "U10") (pin "A12") (pinfunction "P0.02/AIN0_A12") (pintype "bidirectional"))
      (node (ref "U2") (pin "18") (pinfunction "VBAT_SEC_18") (pintype "bidirectional"))
    )
    (net (code "68") (name "VSOL") (class "Default")
      (node (ref "C40") (pin "1") (pinfunction "1_1") (pintype "bidirectional"))
      (node (ref "D1") (pin "+") (pinfunction "V+_+") (pintype "bidirectional"))
      (node (ref "J3") (pin "7") (pinfunction "7_7") (pintype "passive"))
      (node (ref "L7") (pin "P$2") (pinfunction "2_P$2") (pintype "bidirectional"))
      (node (ref "U10") (pin "A10") (pinfunction "P0.29/AIN5_A10") (pintype "bidirectional"))
      (node (ref "U2") (pin "2") (pinfunction "VIN_DC_2") (pintype "bidirectional"))
    )
    (net (code "69") (name "VSW") (class "Default")
      (node (ref "C37") (pin "1") (pinfunction "1_1") (pintype "bidirectional"))
      (node (ref "L8") (pin "P$1") (pinfunction "1_P$1") (pintype "bidirectional"))
      (node (ref "Q5") (pin "3") (pinfunction "D_3") (pintype "passive"))
      (node (ref "Q6") (pin "3") (pinfunction "D_3") (pintype "passive"))
      (node (ref "R22") (pin "2") (pinfunction "2_2") (pintype "passive"))
      (node (ref "TP10") (pin "TESTPOINT") (pinfunction "TESTPOINT_TESTPOINT") (pintype "bidirectional"))
      (node (ref "U6") (pin "5") (pinfunction "IN_5") (pintype "bidirectional"))
    )
    (net (code "70") (name "WDI") (class "Default")
      (node (ref "J3") (pin "3") (pinfunction "3_3") (pintype "passive"))
      (node (ref "R1") (pin "1") (pinfunction "1_1") (pintype "passive"))
      (node (ref "U1") (pin "2") (pinfunction "WDI_2") (pintype "bidirectional"))
      (node (ref "U10") (pin "A8") (pinfunction "P0.31/AIN7_A8") (pintype "bidirectional"))
    )
    (net (code "71") (name "unconnected-(J1-SWO-Pad6)") (class "Default")
      (node (ref "J1") (pin "6") (pinfunction "SWO_6") (pintype "bidirectional"))
    )
    (net (code "72") (name "unconnected-(U1-EXTI-Pad10)") (class "Default")
      (node (ref "U1") (pin "10") (pinfunction "EXTI_10") (pintype "bidirectional"))
    )
    (net (code "73") (name "unconnected-(U1-VBAT-Pad5)") (class "Default")
      (node (ref "U1") (pin "5") (pinfunction "VBAT_5") (pintype "bidirectional"))
    )
    (net (code "74") (name "unconnected-(U2-VBAT_OK-Pad13)") (class "Default")
      (node (ref "U2") (pin "13") (pinfunction "VBAT_OK_13") (pintype "bidirectional"))
    )
    (net (code "75") (name "unconnected-(U2-~{EN}-Pad5)") (class "Default")
      (node (ref "U2") (pin "5") (pinfunction "~{EN}_5") (pintype "bidirectional"))
    )
    (net (code "76") (name "unconnected-(U10-D+-PadAD6)") (class "Default")
      (node (ref "U10") (pin "AD6") (pinfunction "D+_AD6") (pintype "bidirectional"))
    )
    (net (code "77") (name "unconnected-(U10-D--PadAD4)") (class "Default")
      (node (ref "U10") (pin "AD4") (pinfunction "D-_AD4") (pintype "bidirectional"))
    )
    (net (code "78") (name "unconnected-(U10-DCCH-PadAB2)") (class "Default")
      (node (ref "U10") (pin "AB2") (pinfunction "DCCH_AB2") (pintype "bidirectional"))
    )
    (net (code "79") (name "unconnected-(U10-DEC2-PadA18)") (class "Default")
      (node (ref "U10") (pin "A18") (pinfunction "DEC2_A18") (pintype "bidirectional"))
    )
    (net (code "80") (name "unconnected-(U10-DEC5-PadN24)") (class "Default")
      (node (ref "U10") (pin "N24") (pinfunction "DEC5_N24") (pintype "bidirectional"))
    )
    (net (code "81") (name "unconnected-(U10-DECUSB-PadAC5)") (class "Default")
      (node (ref "U10") (pin "AC5") (pinfunction "DECUSB_AC5") (pintype "bidirectional"))
    )
    (net (code "82") (name "unconnected-(U10-P0.03{slash}AIN1-PadB13)") (class "Default")
      (node (ref "U10") (pin "B13") (pinfunction "P0.03/AIN1_B13") (pintype "bidirectional"))
    )
    (net (code "83") (name "unconnected-(U10-P0.05{slash}AIN3-PadK2)") (class "Default")
      (node (ref "U10") (pin "K2") (pinfunction "P0.05/AIN3_K2") (pintype "bidirectional"))
    )
    (net (code "84") (name "unconnected-(U10-P0.07-PadM2)") (class "Default")
      (node (ref "U10") (pin "M2") (pinfunction "P0.07_M2") (pintype "bidirectional"))
    )
    (net (code "85") (name "unconnected-(U10-P0.10{slash}NFC2-PadJ24)") (class "Default")
      (node (ref "U10") (pin "J24") (pinfunction "P0.10/NFC2_J24") (pintype "bidirectional"))
    )
    (net (code "86") (name "unconnected-(U10-P0.16-PadAC11)") (class "Default")
      (node (ref "U10") (pin "AC11") (pinfunction "P0.16_AC11") (pintype "bidirectional"))
    )
    (net (code "87") (name "unconnected-(U10-P0.19-PadAC15)") (class "Default")
      (node (ref "U10") (pin "AC15") (pinfunction "P0.19_AC15") (pintype "bidirectional"))
    )
    (net (code "88") (name "unconnected-(U10-P0.21-PadAC17)") (class "Default")
      (node (ref "U10") (pin "AC17") (pinfunction "P0.21_AC17") (pintype "bidirectional"))
    )
    (net (code "89") (name "unconnected-(U10-P0.23-PadAC19)") (class "Default")
      (node (ref "U10") (pin "AC19") (pinfunction "P0.23_AC19") (pintype "bidirectional"))
    )
    (net (code "90") (name "unconnected-(U10-P0.25-PadAC21)") (class "Default")
      (node (ref "U10") (pin "AC21") (pinfunction "P0.25_AC21") (pintype "bidirectional"))
    )
    (net (code "91") (name "unconnected-(U10-P0.27-PadH2)") (class "Default")
      (node (ref "U10") (pin "H2") (pinfunction "P0.27_H2") (pintype "bidirectional"))
    )
    (net (code "92") (name "unconnected-(U10-P0.28{slash}AIN4-PadB11)") (class "Default")
      (node (ref "U10") (pin "B11") (pinfunction "P0.28/AIN4_B11") (pintype "bidirectional"))
    )
    (net (code "93") (name "unconnected-(U10-P0.30{slash}AIN6-PadB9)") (class "Default")
      (node (ref "U10") (pin "B9") (pinfunction "P0.30/AIN6_B9") (pintype "bidirectional"))
    )
    (net (code "94") (name "unconnected-(U10-P1.03-PadV23)") (class "Default")
      (node (ref "U10") (pin "V23") (pinfunction "P1.03_V23") (pintype "bidirectional"))
    )
    (net (code "95") (name "unconnected-(U10-P1.05-PadT23)") (class "Default")
      (node (ref "U10") (pin "T23") (pinfunction "P1.05_T23") (pintype "bidirectional"))
    )
    (net (code "96") (name "unconnected-(U10-P1.08-PadP2)") (class "Default")
      (node (ref "U10") (pin "P2") (pinfunction "P1.08_P2") (pintype "bidirectional"))
    )
    (net (code "97") (name "unconnected-(U10-P1.09-PadR1)") (class "Default")
      (node (ref "U10") (pin "R1") (pinfunction "P1.09_R1") (pintype "bidirectional"))
    )
    (net (code "98") (name "unconnected-(U10-P1.12-PadB17)") (class "Default")
      (node (ref "U10") (pin "B17") (pinfunction "P1.12_B17") (pintype "bidirectional"))
    )
    (net (code "99") (name "unconnected-(U10-P1.14-PadB15)") (class "Default")
      (node (ref "U10") (pin "B15") (pinfunction "P1.14_B15") (pintype "bidirectional"))
    )
    (net (code "100") (name "unconnected-(U10-P1.15-PadA14)") (class "Default")
      (node (ref "U10") (pin "A14") (pinfunction "P1.15_A14") (pintype "bidirectional"))
    )
    (net (code "101") (name "unconnected-(U12-CBUS0-Pad22)") (class "Default")
      (node (ref "U12") (pin "22") (pinfunction "CBUS0_22") (pintype "bidirectional"))
    )
    (net (code "102") (name "unconnected-(U12-CBUS1-Pad21)") (class "Default")
      (node (ref "U12") (pin "21") (pinfunction "CBUS1_21") (pintype "bidirectional"))
    )
    (net (code "103") (name "unconnected-(U12-CBUS2-Pad10)") (class "Default")
      (node (ref "U12") (pin "10") (pinfunction "CBUS2_10") (pintype "bidirectional"))
    )
    (net (code "104") (name "unconnected-(U12-CBUS3-Pad11)") (class "Default")
      (node (ref "U12") (pin "11") (pinfunction "CBUS3_11") (pintype "bidirectional"))
    )
    (net (code "105") (name "unconnected-(U12-CBUS4-Pad9)") (class "Default")
      (node (ref "U12") (pin "9") (pinfunction "CBUS4_9") (pintype "bidirectional"))
    )
    (net (code "106") (name "unconnected-(U12-OSCI-Pad27)") (class "Default")
      (node (ref "U12") (pin "27") (pinfunction "OSCI_27") (pintype "input"))
    )
    (net (code "107") (name "unconnected-(U12-OSCO-Pad28)") (class "Default")
      (node (ref "U12") (pin "28") (pinfunction "OSCO_28") (pintype "output"))
    )
    (net (code "108") (name "unconnected-(U12-~{CTS}-Pad8)") (class "Default")
      (node (ref "U12") (pin "8") (pinfunction "~{CTS}_8") (pintype "input"))
    )
    (net (code "109") (name "unconnected-(U12-~{DCD}-Pad7)") (class "Default")
      (node (ref "U12") (pin "7") (pinfunction "~{DCD}_7") (pintype "input"))
    )
    (net (code "110") (name "unconnected-(U12-~{DSR}-Pad6)") (class "Default")
      (node (ref "U12") (pin "6") (pinfunction "~{DSR}_6") (pintype "input"))
    )
    (net (code "111") (name "unconnected-(U12-~{DTR}-Pad31)") (class "Default")
      (node (ref "U12") (pin "31") (pinfunction "~{DTR}_31") (pintype "output"))
    )
    (net (code "112") (name "unconnected-(U12-~{RI}-Pad3)") (class "Default")
      (node (ref "U12") (pin "3") (pinfunction "~{RI}_3") (pintype "input"))
    )
    (net (code "113") (name "unconnected-(U12-~{RTS}-Pad32)") (class "Default")
      (node (ref "U12") (pin "32") (pinfunction "~{RTS}_32") (pintype "output"))
    )
    (net (code "114") (name "~{ACC_EN}") (class "Default")
      (node (ref "J2") (pin "15") (pinfunction "15_15") (pintype "passive"))
    )
    (net (code "115") (name "~{CLR_EN}") (class "Default")
      (node (ref "J2") (pin "9") (pinfunction "9_9") (pintype "passive"))
      (node (ref "Q4") (pin "2") (pinfunction "G_2") (pintype "passive"))
      (node (ref "Q4") (pin "5") (pinfunction "G_5") (pintype "passive"))
      (node (ref "Q7") (pin "2") (pinfunction "G_2") (pintype "passive"))
      (node (ref "R23") (pin "1") (pinfunction "1_1") (pintype "passive"))
      (node (ref "U10") (pin "T2") (pinfunction "P0.11_T2") (pintype "bidirectional"))
    )
    (net (code "116") (name "~{CLR_INT}") (class "Default")
      (node (ref "J2") (pin "10") (pinfunction "10_10") (pintype "passive"))
      (node (ref "R4") (pin "1") (pinfunction "1_1") (pintype "passive"))
      (node (ref "U10") (pin "W24") (pinfunction "P1.02_W24") (pintype "bidirectional"))
      (node (ref "U4") (pin "5") (pinfunction "~{INT}_5") (pintype "bidirectional"))
    )
    (net (code "117") (name "~{HUM_EN}") (class "Default")
      (node (ref "J2") (pin "8") (pinfunction "8_8") (pintype "passive"))
      (node (ref "Q2") (pin "2") (pinfunction "G_2") (pintype "passive"))
      (node (ref "Q2") (pin "5") (pinfunction "G_5") (pintype "passive"))
      (node (ref "Q8") (pin "5") (pinfunction "G_5") (pintype "passive"))
      (node (ref "R26") (pin "1") (pinfunction "1_1") (pintype "passive"))
      (node (ref "U10") (pin "U1") (pinfunction "P0.12_U1") (pintype "bidirectional"))
    )
    (net (code "118") (name "~{I2C_EN}") (class "Default")
      (node (ref "J2") (pin "3") (pinfunction "3_3") (pintype "passive"))
    )
    (net (code "119") (name "~{LT_EN}") (class "Default")
      (node (ref "J2") (pin "11") (pinfunction "11_11") (pintype "passive"))
      (node (ref "Q3") (pin "2") (pinfunction "G_2") (pintype "passive"))
      (node (ref "Q3") (pin "5") (pinfunction "G_5") (pintype "passive"))
      (node (ref "Q7") (pin "5") (pinfunction "G_5") (pintype "passive"))
      (node (ref "R24") (pin "1") (pinfunction "1_1") (pintype "passive"))
      (node (ref "U10") (pin "A16") (pinfunction "P1.13_A16") (pintype "bidirectional"))
    )
    (net (code "120") (name "~{LT_INT}") (class "Default")
      (node (ref "J2") (pin "12") (pinfunction "12_12") (pintype "passive"))
      (node (ref "R5") (pin "1") (pinfunction "1_1") (pintype "passive"))
      (node (ref "U10") (pin "U24") (pinfunction "P1.04_U24") (pintype "bidirectional"))
      (node (ref "U7") (pin "4") (pinfunction "~{INT}_4") (pintype "bidirectional"))
    )
    (net (code "121") (name "~{PIR_EN}") (class "Default")
      (node (ref "J2") (pin "13") (pinfunction "13_13") (pintype "passive"))
      (node (ref "Q10") (pin "2") (pinfunction "G_2") (pintype "passive"))
      (node (ref "R27") (pin "1") (pinfunction "1_1") (pintype "passive"))
      (node (ref "U10") (pin "A20") (pinfunction "P1.10_A20") (pintype "bidirectional"))
    )
    (net (code "122") (name "~{PR_EN}") (class "Default")
      (node (ref "J2") (pin "7") (pinfunction "7_7") (pintype "passive"))
      (node (ref "Q1") (pin "2") (pinfunction "G_2") (pintype "passive"))
      (node (ref "Q1") (pin "5") (pinfunction "G_5") (pintype "passive"))
      (node (ref "Q8") (pin "2") (pinfunction "G_2") (pintype "passive"))
      (node (ref "R25") (pin "1") (pinfunction "1_1") (pintype "passive"))
      (node (ref "U10") (pin "B19") (pinfunction "P1.11_B19") (pintype "bidirectional"))
    )
    (net (code "123") (name "~{RST}") (class "Default")
      (node (ref "J1") (pin "3") (pinfunction "~{RESET}_3") (pintype "bidirectional"))
      (node (ref "J3") (pin "4") (pinfunction "4_4") (pintype "passive"))
      (node (ref "R7") (pin "1") (pinfunction "1_1") (pintype "passive"))
      (node (ref "U1") (pin "1") (pinfunction "~{RST}_1") (pintype "bidirectional"))
      (node (ref "U10") (pin "AC13") (pinfunction "P0.18_AC13") (pintype "bidirectional"))
      (node (ref "U10") (pin "AD12") (pinfunction "P0.17_AD12") (pintype "bidirectional"))
      (node (ref "U12") (pin "18") (pinfunction "~{RESET}_18") (pintype "input"))
    )
    (net (code "124") (name "~{RTC_IRQ1}") (class "Default")
      (node (ref "J2") (pin "19") (pinfunction "19_19") (pintype "passive"))
      (node (ref "U1") (pin "11") (pinfunction "FOUT/~{IRQ1}_11") (pintype "bidirectional"))
      (node (ref "U10") (pin "AC9") (pinfunction "P0.14_AC9") (pintype "bidirectional"))
    )
    (net (code "125") (name "~{RTC_IRQ2}") (class "Default")
      (node (ref "J2") (pin "20") (pinfunction "20_20") (pintype "passive"))
      (node (ref "U1") (pin "4") (pinfunction "~{IRQ2}_4") (pintype "bidirectional"))
      (node (ref "U10") (pin "AD16") (pinfunction "P0.20_AD16") (pintype "bidirectional"))
    )
    (net (code "126") (name "~{RTC_IRQ3}") (class "Default")
      (node (ref "J3") (pin "1") (pinfunction "1_1") (pintype "passive"))
      (node (ref "U1") (pin "8") (pinfunction "CLKOUT/~{IRQ3}_8") (pintype "bidirectional"))
      (node (ref "U10") (pin "P23") (pinfunction "P1.07_P23") (pintype "bidirectional"))
    )
  )
)
